# ccnor_stm32_v24-sync.net
KiCad netlist of a schematic drawn in EAGLE
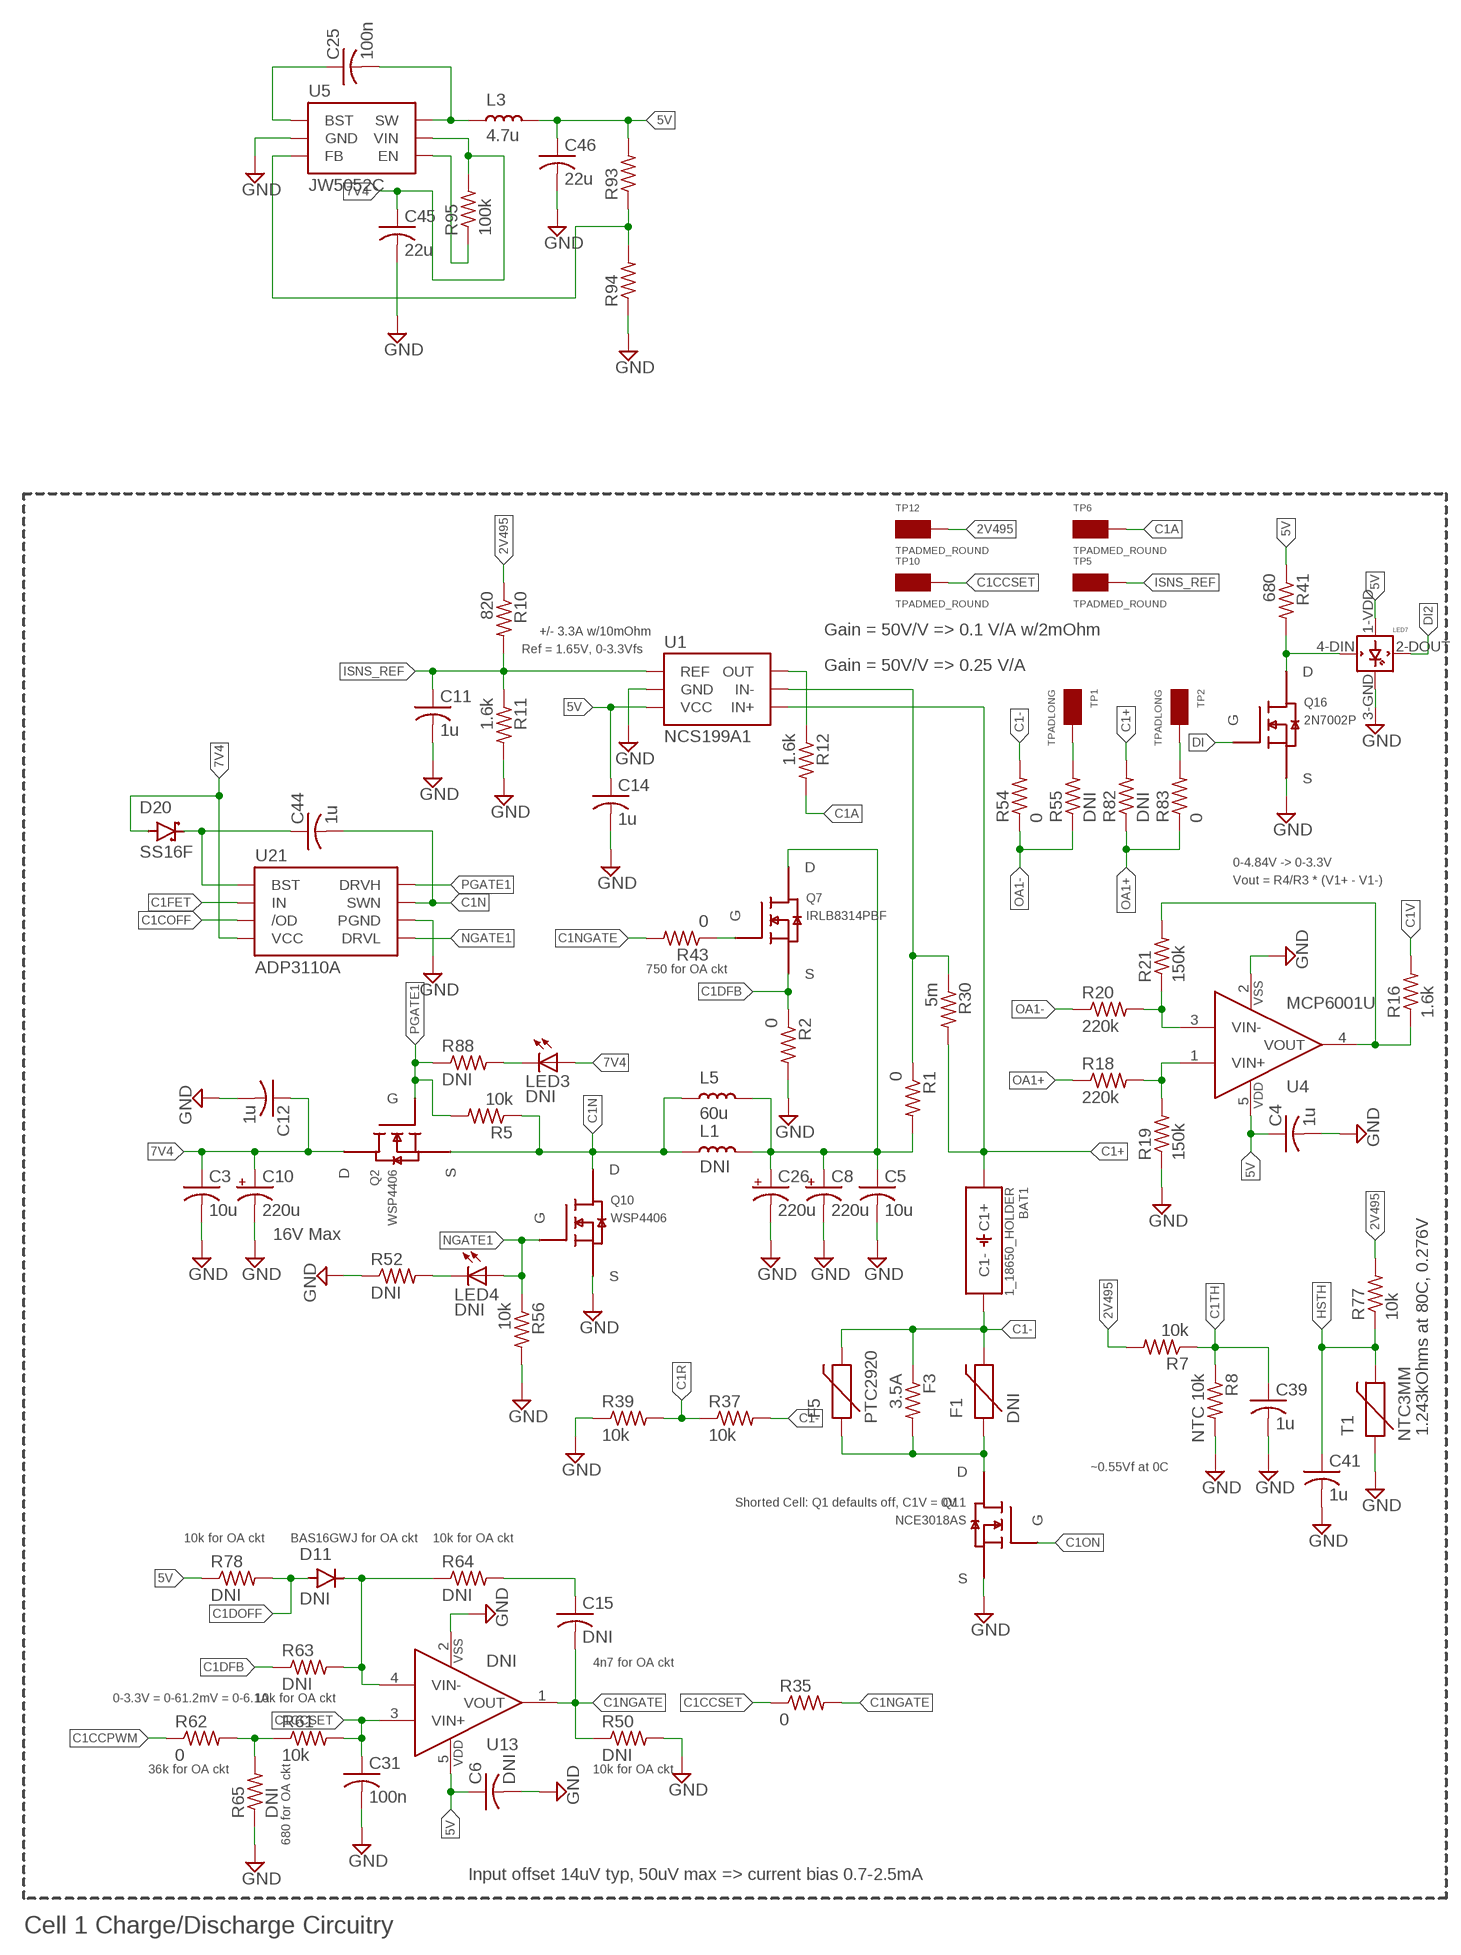
[diagram p0: schematic, sheet 1, part 1 of 2]
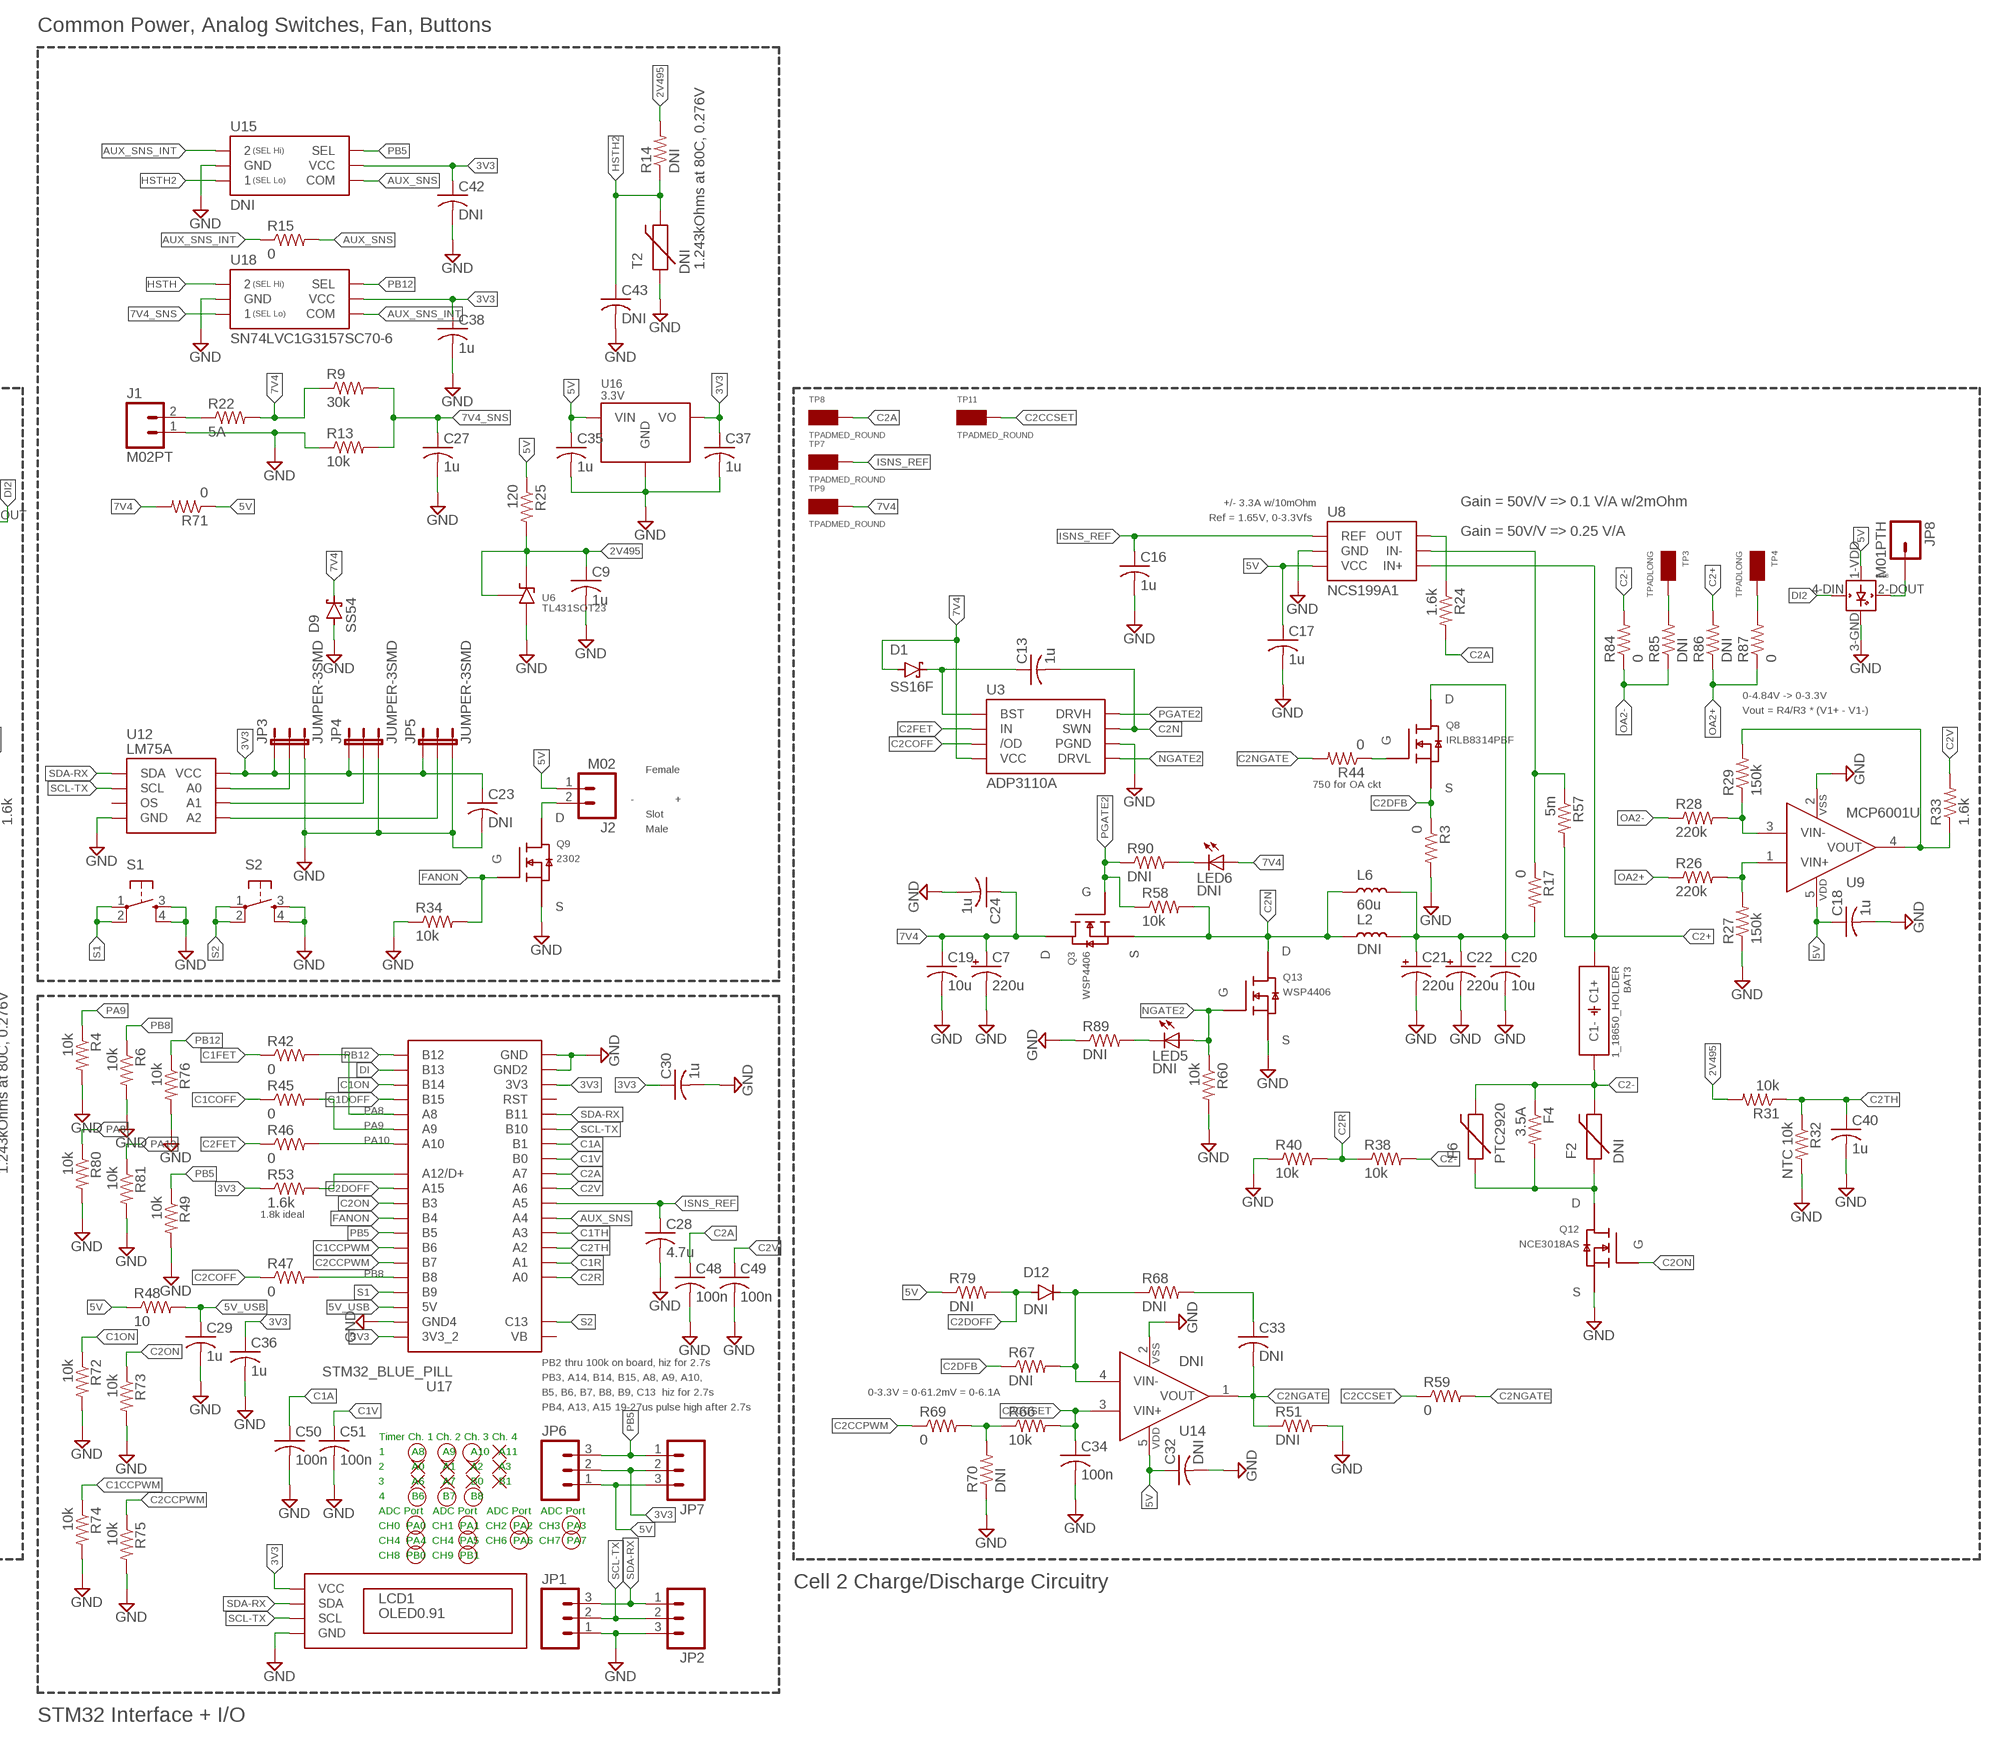
[diagram p1: schematic, sheet 1, part 2 of 2]

(export (version "E")
  (design (tool "Eeschema 10.0.6"))
  (components
    (comp (ref "BAT1")
      (value "1_18650_HOLDER")
      (footprint "eagle-import:1S_18650_SMD_NH")
      (libsource (lib "eagle-import") (part "1_18650_HOLDER"))
    )
    (comp (ref "BAT3")
      (value "1_18650_HOLDER")
      (footprint "eagle-import:1S_18650_SMD_NH")
      (libsource (lib "eagle-import") (part "1_18650_HOLDER"))
    )
    (comp (ref "C3")
      (value "10u")
      (footprint "eagle-import:C1206")
      (libsource (lib "eagle-import") (part "C-USC1206"))
    )
    (comp (ref "C4")
      (value "1u")
      (footprint "eagle-import:C0402")
      (libsource (lib "eagle-import") (part "C-USC0402"))
    )
    (comp (ref "C5")
      (value "10u")
      (footprint "eagle-import:C1206")
      (libsource (lib "eagle-import") (part "C-USC1206"))
    )
    (comp (ref "C6")
      (value "DNI")
      (footprint "eagle-import:C0402")
      (libsource (lib "eagle-import") (part "C-USC0402"))
    )
    (comp (ref "C7")
      (value "220u")
      (footprint "eagle-import:PANASONIC_D")
      (libsource (lib "eagle-import") (part "CPOL-USD"))
    )
    (comp (ref "C8")
      (value "220u")
      (footprint "eagle-import:PANASONIC_D")
      (libsource (lib "eagle-import") (part "CPOL-USD"))
    )
    (comp (ref "C9")
      (value "1u")
      (footprint "eagle-import:C0402")
      (libsource (lib "eagle-import") (part "C-USC0402"))
    )
    (comp (ref "C10")
      (value "220u")
      (footprint "eagle-import:PANASONIC_D")
      (libsource (lib "eagle-import") (part "CPOL-USD"))
    )
    (comp (ref "C11")
      (value "1u")
      (footprint "eagle-import:C0402")
      (libsource (lib "eagle-import") (part "C-USC0402"))
    )
    (comp (ref "C12")
      (value "1u")
      (footprint "eagle-import:C0402")
      (libsource (lib "eagle-import") (part "C-USC0402"))
    )
    (comp (ref "C13")
      (value "1u")
      (footprint "eagle-import:C0603")
      (libsource (lib "eagle-import") (part "C-USC0603"))
    )
    (comp (ref "C14")
      (value "1u")
      (footprint "eagle-import:C0402")
      (libsource (lib "eagle-import") (part "C-USC0402"))
    )
    (comp (ref "C15")
      (value "DNI")
      (footprint "eagle-import:C0402")
      (libsource (lib "eagle-import") (part "C-USC0402"))
    )
    (comp (ref "C16")
      (value "1u")
      (footprint "eagle-import:C0402")
      (libsource (lib "eagle-import") (part "C-USC0402"))
    )
    (comp (ref "C17")
      (value "1u")
      (footprint "eagle-import:C0402")
      (libsource (lib "eagle-import") (part "C-USC0402"))
    )
    (comp (ref "C18")
      (value "1u")
      (footprint "eagle-import:C0402")
      (libsource (lib "eagle-import") (part "C-USC0402"))
    )
    (comp (ref "C19")
      (value "10u")
      (footprint "eagle-import:C1206")
      (libsource (lib "eagle-import") (part "C-USC1206"))
    )
    (comp (ref "C20")
      (value "10u")
      (footprint "eagle-import:C1206")
      (libsource (lib "eagle-import") (part "C-USC1206"))
    )
    (comp (ref "C21")
      (value "220u")
      (footprint "eagle-import:PANASONIC_D")
      (libsource (lib "eagle-import") (part "CPOL-USD"))
    )
    (comp (ref "C22")
      (value "220u")
      (footprint "eagle-import:PANASONIC_D")
      (libsource (lib "eagle-import") (part "CPOL-USD"))
    )
    (comp (ref "C23")
      (value "DNI")
      (footprint "eagle-import:C0402")
      (libsource (lib "eagle-import") (part "C-USC0402"))
    )
    (comp (ref "C24")
      (value "1u")
      (footprint "eagle-import:C0402")
      (libsource (lib "eagle-import") (part "C-USC0402"))
    )
    (comp (ref "C25")
      (value "100n")
      (footprint "eagle-import:C0402")
      (libsource (lib "eagle-import") (part "C-USC0402"))
    )
    (comp (ref "C26")
      (value "220u")
      (footprint "eagle-import:PANASONIC_D")
      (libsource (lib "eagle-import") (part "CPOL-USD"))
    )
    (comp (ref "C27")
      (value "1u")
      (footprint "eagle-import:C0402")
      (libsource (lib "eagle-import") (part "C-USC0402"))
    )
    (comp (ref "C28")
      (value "4.7u")
      (footprint "eagle-import:C0402")
      (libsource (lib "eagle-import") (part "C-USC0402"))
    )
    (comp (ref "C29")
      (value "1u")
      (footprint "eagle-import:C0402")
      (libsource (lib "eagle-import") (part "C-USC0402"))
    )
    (comp (ref "C30")
      (value "1u")
      (footprint "eagle-import:C0402")
      (libsource (lib "eagle-import") (part "C-USC0402"))
    )
    (comp (ref "C31")
      (value "100n")
      (footprint "eagle-import:C0402")
      (libsource (lib "eagle-import") (part "C-USC0402"))
    )
    (comp (ref "C32")
      (value "DNI")
      (footprint "eagle-import:C0402")
      (libsource (lib "eagle-import") (part "C-USC0402"))
    )
    (comp (ref "C33")
      (value "DNI")
      (footprint "eagle-import:C0402")
      (libsource (lib "eagle-import") (part "C-USC0402"))
    )
    (comp (ref "C34")
      (value "100n")
      (footprint "eagle-import:C0402")
      (libsource (lib "eagle-import") (part "C-USC0402"))
    )
    (comp (ref "C35")
      (value "1u")
      (footprint "eagle-import:C0402")
      (libsource (lib "eagle-import") (part "C-USC0402"))
    )
    (comp (ref "C36")
      (value "1u")
      (footprint "eagle-import:C0402")
      (libsource (lib "eagle-import") (part "C-USC0402"))
    )
    (comp (ref "C37")
      (value "1u")
      (footprint "eagle-import:C0402")
      (libsource (lib "eagle-import") (part "C-USC0402"))
    )
    (comp (ref "C38")
      (value "1u")
      (footprint "eagle-import:C0402")
      (libsource (lib "eagle-import") (part "C-USC0402"))
    )
    (comp (ref "C39")
      (value "1u")
      (footprint "eagle-import:C0402")
      (libsource (lib "eagle-import") (part "C-USC0402"))
    )
    (comp (ref "C40")
      (value "1u")
      (footprint "eagle-import:C0402")
      (libsource (lib "eagle-import") (part "C-USC0402"))
    )
    (comp (ref "C41")
      (value "1u")
      (footprint "eagle-import:C0402")
      (libsource (lib "eagle-import") (part "C-USC0402"))
    )
    (comp (ref "C42")
      (value "DNI")
      (footprint "eagle-import:C0402")
      (libsource (lib "eagle-import") (part "C-USC0402"))
    )
    (comp (ref "C43")
      (value "DNI")
      (footprint "eagle-import:C0402")
      (libsource (lib "eagle-import") (part "C-USC0402"))
    )
    (comp (ref "C44")
      (value "1u")
      (footprint "eagle-import:C0603")
      (libsource (lib "eagle-import") (part "C-USC0603"))
    )
    (comp (ref "C45")
      (value "22u")
      (footprint "eagle-import:C0805")
      (libsource (lib "eagle-import") (part "C-USC0805"))
    )
    (comp (ref "C46")
      (value "22u")
      (footprint "eagle-import:C0603")
      (libsource (lib "eagle-import") (part "C-USC0603"))
    )
    (comp (ref "C48")
      (value "100n")
      (footprint "eagle-import:C0402")
      (libsource (lib "eagle-import") (part "C-USC0402"))
    )
    (comp (ref "C49")
      (value "100n")
      (footprint "eagle-import:C0402")
      (libsource (lib "eagle-import") (part "C-USC0402"))
    )
    (comp (ref "C50")
      (value "100n")
      (footprint "eagle-import:C0402")
      (libsource (lib "eagle-import") (part "C-USC0402"))
    )
    (comp (ref "C51")
      (value "100n")
      (footprint "eagle-import:C0402")
      (libsource (lib "eagle-import") (part "C-USC0402"))
    )
    (comp (ref "D1")
      (value "SS16F")
      (footprint "eagle-import:SOD123")
      (libsource (lib "eagle-import") (part "DIODE_SCHOTTKYCDBM140-G"))
    )
    (comp (ref "D9")
      (value "SS54")
      (footprint "eagle-import:SMA")
      (libsource (lib "eagle-import") (part "SS54"))
    )
    (comp (ref "D11")
      (value "DNI")
      (footprint "eagle-import:SOD323")
      (libsource (lib "eagle-import") (part "BAT60A"))
    )
    (comp (ref "D12")
      (value "DNI")
      (footprint "eagle-import:SOD323")
      (libsource (lib "eagle-import") (part "BAT60A"))
    )
    (comp (ref "D20")
      (value "SS16F")
      (footprint "eagle-import:SOD123")
      (libsource (lib "eagle-import") (part "DIODE_SCHOTTKYCDBM140-G"))
    )
    (comp (ref "F1")
      (value "DNI")
      (footprint "eagle-import:1812")
      (libsource (lib "eagle-import") (part "PTC1812"))
    )
    (comp (ref "F2")
      (value "DNI")
      (footprint "eagle-import:1812")
      (libsource (lib "eagle-import") (part "PTC1812"))
    )
    (comp (ref "F3")
      (value "3.5A")
      (footprint "eagle-import:R1206")
      (libsource (lib "eagle-import") (part "R-US_R1206"))
    )
    (comp (ref "F4")
      (value "3.5A")
      (footprint "eagle-import:R1206")
      (libsource (lib "eagle-import") (part "R-US_R1206"))
    )
    (comp (ref "F5")
      (value "PTC2920")
      (footprint "eagle-import:2920")
      (libsource (lib "eagle-import") (part "PTC2920"))
    )
    (comp (ref "F6")
      (value "PTC2920")
      (footprint "eagle-import:2920")
      (libsource (lib "eagle-import") (part "PTC2920"))
    )
    (comp (ref "J1")
      (value "M02PT")
      (footprint "eagle-import:PHOENIXCONTACT1935161")
      (libsource (lib "eagle-import") (part "M02PT"))
    )
    (comp (ref "J2")
      (value "M02")
      (footprint "eagle-import:B2B-XH-A")
      (libsource (lib "eagle-import") (part "M02"))
    )
    (comp (ref "JP1")
      (value "M03PTH")
      (footprint "eagle-import:1X03")
      (libsource (lib "eagle-import") (part "M03PTH"))
    )
    (comp (ref "JP2")
      (value "M03PTH")
      (footprint "eagle-import:1X03")
      (libsource (lib "eagle-import") (part "M03PTH"))
    )
    (comp (ref "JP3")
      (value "JUMPER-3SMD")
      (footprint "eagle-import:SJ_3")
      (libsource (lib "eagle-import") (part "JUMPER-3SMD"))
    )
    (comp (ref "JP4")
      (value "JUMPER-3SMD")
      (footprint "eagle-import:SJ_3")
      (libsource (lib "eagle-import") (part "JUMPER-3SMD"))
    )
    (comp (ref "JP5")
      (value "JUMPER-3SMD")
      (footprint "eagle-import:SJ_3")
      (libsource (lib "eagle-import") (part "JUMPER-3SMD"))
    )
    (comp (ref "JP6")
      (value "M03PTH")
      (footprint "eagle-import:1X03")
      (libsource (lib "eagle-import") (part "M03PTH"))
    )
    (comp (ref "JP7")
      (value "M03PTH")
      (footprint "eagle-import:1X03")
      (libsource (lib "eagle-import") (part "M03PTH"))
    )
    (comp (ref "JP8")
      (value "M01PTH")
      (footprint "eagle-import:1X01")
      (libsource (lib "eagle-import") (part "M01PTH"))
    )
    (comp (ref "L1")
      (value "DNI")
      (footprint "eagle-import:INDUCTOR_SMD_13MM")
      (libsource (lib "eagle-import") (part "SDR1307"))
    )
    (comp (ref "L2")
      (value "DNI")
      (footprint "eagle-import:INDUCTOR_SMD_13MM")
      (libsource (lib "eagle-import") (part "SDR1307"))
    )
    (comp (ref "L3")
      (value "4.7u")
      (footprint "eagle-import:0805")
      (libsource (lib "eagle-import") (part "INDUCTOR0805"))
    )
    (comp (ref "L5")
      (value "60u")
      (footprint "eagle-import:INDUCTOR_10A_8.2MMX21MM")
      (libsource (lib "eagle-import") (part "INDUCTOR10A"))
    )
    (comp (ref "L6")
      (value "60u")
      (footprint "eagle-import:INDUCTOR_10A_8.2MMX21MM")
      (libsource (lib "eagle-import") (part "INDUCTOR10A"))
    )
    (comp (ref "LCD1")
      (value "OLED0.91")
      (footprint "eagle-import:OLED0.91")
      (libsource (lib "eagle-import") (part "OLED0.91"))
    )
    (comp (ref "LED3")
      (value "DNI")
      (footprint "eagle-import:CHIPLED_0603")
      (libsource (lib "eagle-import") (part "LEDCHIPLED_0603"))
    )
    (comp (ref "LED4")
      (value "DNI")
      (footprint "eagle-import:CHIPLED_0603")
      (libsource (lib "eagle-import") (part "LEDCHIPLED_0603"))
    )
    (comp (ref "LED5")
      (value "DNI")
      (footprint "eagle-import:CHIPLED_0603")
      (libsource (lib "eagle-import") (part "LEDCHIPLED_0603"))
    )
    (comp (ref "LED6")
      (value "DNI")
      (footprint "eagle-import:CHIPLED_0603")
      (libsource (lib "eagle-import") (part "LEDCHIPLED_0603"))
    )
    (comp (ref "LED7")
      (value "WS2812B")
      (footprint "eagle-import:WS2812B")
      (libsource (lib "eagle-import") (part "WS2812B"))
    )
    (comp (ref "LED8")
      (value "WS2812B")
      (footprint "eagle-import:WS2812B")
      (libsource (lib "eagle-import") (part "WS2812B"))
    )
    (comp (ref "Q2")
      (value "WSP4406")
      (footprint "eagle-import:8-SOIC")
      (libsource (lib "eagle-import") (part "N-MOSFET-SOIC8"))
    )
    (comp (ref "Q3")
      (value "WSP4406")
      (footprint "eagle-import:8-SOIC")
      (libsource (lib "eagle-import") (part "N-MOSFET-SOIC8"))
    )
    (comp (ref "Q7")
      (value "IRLB8314PBF")
      (footprint "eagle-import:TO-220")
      (libsource (lib "eagle-import") (part "IRLB8314PBF"))
    )
    (comp (ref "Q8")
      (value "IRLB8314PBF")
      (footprint "eagle-import:TO-220")
      (libsource (lib "eagle-import") (part "IRLB8314PBF"))
    )
    (comp (ref "Q9")
      (value "2302")
      (footprint "eagle-import:SOT23")
      (libsource (lib "eagle-import") (part "2N7002P"))
    )
    (comp (ref "Q10")
      (value "WSP4406")
      (footprint "eagle-import:8-SOIC")
      (libsource (lib "eagle-import") (part "N-MOSFET-SOIC8"))
    )
    (comp (ref "Q11")
      (value "NCE3018AS")
      (footprint "eagle-import:8-SOIC")
      (libsource (lib "eagle-import") (part "N-MOSFET-SOIC8"))
    )
    (comp (ref "Q12")
      (value "NCE3018AS")
      (footprint "eagle-import:8-SOIC")
      (libsource (lib "eagle-import") (part "N-MOSFET-SOIC8"))
    )
    (comp (ref "Q13")
      (value "WSP4406")
      (footprint "eagle-import:8-SOIC")
      (libsource (lib "eagle-import") (part "N-MOSFET-SOIC8"))
    )
    (comp (ref "Q16")
      (value "2N7002P")
      (footprint "eagle-import:SOT23")
      (libsource (lib "eagle-import") (part "2N7002P"))
    )
    (comp (ref "R1")
      (value "0")
      (footprint "eagle-import:R1206")
      (libsource (lib "eagle-import") (part "R-US_R1206"))
    )
    (comp (ref "R2")
      (value "0")
      (footprint "eagle-import:R1206")
      (libsource (lib "eagle-import") (part "R-US_R1206"))
    )
    (comp (ref "R3")
      (value "0")
      (footprint "eagle-import:R1206")
      (libsource (lib "eagle-import") (part "R-US_R1206"))
    )
    (comp (ref "R4")
      (value "10k")
      (footprint "eagle-import:R0402")
      (libsource (lib "eagle-import") (part "R-US_R0402"))
    )
    (comp (ref "R5")
      (value "10k")
      (footprint "eagle-import:R0402")
      (libsource (lib "eagle-import") (part "R-US_R0402"))
    )
    (comp (ref "R6")
      (value "10k")
      (footprint "eagle-import:R0402")
      (libsource (lib "eagle-import") (part "R-US_R0402"))
    )
    (comp (ref "R7")
      (value "10k")
      (footprint "eagle-import:R0402")
      (libsource (lib "eagle-import") (part "R-US_R0402"))
    )
    (comp (ref "R8")
      (value "NTC 10k")
      (footprint "eagle-import:R0402")
      (libsource (lib "eagle-import") (part "R-US_R0402"))
    )
    (comp (ref "R9")
      (value "30k")
      (footprint "eagle-import:R0402")
      (libsource (lib "eagle-import") (part "R-US_R0402"))
    )
    (comp (ref "R10")
      (value "820")
      (footprint "eagle-import:R0402")
      (libsource (lib "eagle-import") (part "R-US_R0402"))
    )
    (comp (ref "R11")
      (value "1.6k")
      (footprint "eagle-import:R0402")
      (libsource (lib "eagle-import") (part "R-US_R0402"))
    )
    (comp (ref "R12")
      (value "1.6k")
      (footprint "eagle-import:R0402")
      (libsource (lib "eagle-import") (part "R-US_R0402"))
    )
    (comp (ref "R13")
      (value "10k")
      (footprint "eagle-import:R0402")
      (libsource (lib "eagle-import") (part "R-US_R0402"))
    )
    (comp (ref "R14")
      (value "DNI")
      (footprint "eagle-import:R0402")
      (libsource (lib "eagle-import") (part "R-US_R0402"))
    )
    (comp (ref "R15")
      (value "0")
      (footprint "eagle-import:R0402")
      (libsource (lib "eagle-import") (part "R-US_R0402"))
    )
    (comp (ref "R16")
      (value "1.6k")
      (footprint "eagle-import:R0402")
      (libsource (lib "eagle-import") (part "R-US_R0402"))
    )
    (comp (ref "R17")
      (value "0")
      (footprint "eagle-import:R1206")
      (libsource (lib "eagle-import") (part "R-US_R1206"))
    )
    (comp (ref "R18")
      (value "220k")
      (footprint "eagle-import:R0402")
      (libsource (lib "eagle-import") (part "R-US_R0402"))
    )
    (comp (ref "R19")
      (value "150k")
      (footprint "eagle-import:R0402")
      (libsource (lib "eagle-import") (part "R-US_R0402"))
    )
    (comp (ref "R20")
      (value "220k")
      (footprint "eagle-import:R0402")
      (libsource (lib "eagle-import") (part "R-US_R0402"))
    )
    (comp (ref "R21")
      (value "150k")
      (footprint "eagle-import:R0402")
      (libsource (lib "eagle-import") (part "R-US_R0402"))
    )
    (comp (ref "R22")
      (value "5A")
      (footprint "eagle-import:R1206")
      (libsource (lib "eagle-import") (part "R-US_R1206"))
    )
    (comp (ref "R24")
      (value "1.6k")
      (footprint "eagle-import:R0402")
      (libsource (lib "eagle-import") (part "R-US_R0402"))
    )
    (comp (ref "R25")
      (value "120")
      (footprint "eagle-import:R0402")
      (libsource (lib "eagle-import") (part "R-US_R0402"))
    )
    (comp (ref "R26")
      (value "220k")
      (footprint "eagle-import:R0402")
      (libsource (lib "eagle-import") (part "R-US_R0402"))
    )
    (comp (ref "R27")
      (value "150k")
      (footprint "eagle-import:R0402")
      (libsource (lib "eagle-import") (part "R-US_R0402"))
    )
    (comp (ref "R28")
      (value "220k")
      (footprint "eagle-import:R0402")
      (libsource (lib "eagle-import") (part "R-US_R0402"))
    )
    (comp (ref "R29")
      (value "150k")
      (footprint "eagle-import:R0402")
      (libsource (lib "eagle-import") (part "R-US_R0402"))
    )
    (comp (ref "R30")
      (value "5m")
      (footprint "eagle-import:R1206")
      (libsource (lib "eagle-import") (part "R-US_R1206"))
    )
    (comp (ref "R31")
      (value "10k")
      (footprint "eagle-import:R0402")
      (libsource (lib "eagle-import") (part "R-US_R0402"))
    )
    (comp (ref "R32")
      (value "NTC 10k")
      (footprint "eagle-import:R0402")
      (libsource (lib "eagle-import") (part "R-US_R0402"))
    )
    (comp (ref "R33")
      (value "1.6k")
      (footprint "eagle-import:R0402")
      (libsource (lib "eagle-import") (part "R-US_R0402"))
    )
    (comp (ref "R34")
      (value "10k")
      (footprint "eagle-import:R0402")
      (libsource (lib "eagle-import") (part "R-US_R0402"))
    )
    (comp (ref "R35")
      (value "0")
      (footprint "eagle-import:R0402")
      (libsource (lib "eagle-import") (part "R-US_R0402"))
    )
    (comp (ref "R37")
      (value "10k")
      (footprint "eagle-import:R0402")
      (libsource (lib "eagle-import") (part "R-US_R0402"))
    )
    (comp (ref "R38")
      (value "10k")
      (footprint "eagle-import:R0402")
      (libsource (lib "eagle-import") (part "R-US_R0402"))
    )
    (comp (ref "R39")
      (value "10k")
      (footprint "eagle-import:R0402")
      (libsource (lib "eagle-import") (part "R-US_R0402"))
    )
    (comp (ref "R40")
      (value "10k")
      (footprint "eagle-import:R0402")
      (libsource (lib "eagle-import") (part "R-US_R0402"))
    )
    (comp (ref "R41")
      (value "680")
      (footprint "eagle-import:R0402")
      (libsource (lib "eagle-import") (part "R-US_R0402"))
    )
    (comp (ref "R42")
      (value "0")
      (footprint "eagle-import:R0402")
      (libsource (lib "eagle-import") (part "R-US_R0402"))
    )
    (comp (ref "R43")
      (value "0")
      (footprint "eagle-import:R0402")
      (libsource (lib "eagle-import") (part "R-US_R0402"))
    )
    (comp (ref "R44")
      (value "0")
      (footprint "eagle-import:R0402")
      (libsource (lib "eagle-import") (part "R-US_R0402"))
    )
    (comp (ref "R45")
      (value "0")
      (footprint "eagle-import:R0402")
      (libsource (lib "eagle-import") (part "R-US_R0402"))
    )
    (comp (ref "R46")
      (value "0")
      (footprint "eagle-import:R0402")
      (libsource (lib "eagle-import") (part "R-US_R0402"))
    )
    (comp (ref "R47")
      (value "0")
      (footprint "eagle-import:R0402")
      (libsource (lib "eagle-import") (part "R-US_R0402"))
    )
    (comp (ref "R48")
      (value "10")
      (footprint "eagle-import:R0402")
      (libsource (lib "eagle-import") (part "R-US_R0402"))
    )
    (comp (ref "R49")
      (value "10k")
      (footprint "eagle-import:R0402")
      (libsource (lib "eagle-import") (part "R-US_R0402"))
    )
    (comp (ref "R50")
      (value "DNI")
      (footprint "eagle-import:R0402")
      (libsource (lib "eagle-import") (part "R-US_R0402"))
    )
    (comp (ref "R51")
      (value "DNI")
      (footprint "eagle-import:R0402")
      (libsource (lib "eagle-import") (part "R-US_R0402"))
    )
    (comp (ref "R52")
      (value "DNI")
      (footprint "eagle-import:R0402")
      (libsource (lib "eagle-import") (part "R-US_R0402"))
    )
    (comp (ref "R53")
      (value "1.6k")
      (footprint "eagle-import:R0402")
      (libsource (lib "eagle-import") (part "R-US_R0402"))
    )
    (comp (ref "R54")
      (value "0")
      (footprint "eagle-import:R0402")
      (libsource (lib "eagle-import") (part "R-US_R0402"))
    )
    (comp (ref "R55")
      (value "DNI")
      (footprint "eagle-import:R0402")
      (libsource (lib "eagle-import") (part "R-US_R0402"))
    )
    (comp (ref "R56")
      (value "10k")
      (footprint "eagle-import:R0402")
      (libsource (lib "eagle-import") (part "R-US_R0402"))
    )
    (comp (ref "R57")
      (value "5m")
      (footprint "eagle-import:R1206")
      (libsource (lib "eagle-import") (part "R-US_R1206"))
    )
    (comp (ref "R58")
      (value "10k")
      (footprint "eagle-import:R0402")
      (libsource (lib "eagle-import") (part "R-US_R0402"))
    )
    (comp (ref "R59")
      (value "0")
      (footprint "eagle-import:R0402")
      (libsource (lib "eagle-import") (part "R-US_R0402"))
    )
    (comp (ref "R60")
      (value "10k")
      (footprint "eagle-import:R0402")
      (libsource (lib "eagle-import") (part "R-US_R0402"))
    )
    (comp (ref "R61")
      (value "10k")
      (footprint "eagle-import:R0402")
      (libsource (lib "eagle-import") (part "R-US_R0402"))
    )
    (comp (ref "R62")
      (value "0")
      (footprint "eagle-import:R0402")
      (libsource (lib "eagle-import") (part "R-US_R0402"))
    )
    (comp (ref "R63")
      (value "DNI")
      (footprint "eagle-import:R0402")
      (libsource (lib "eagle-import") (part "R-US_R0402"))
    )
    (comp (ref "R64")
      (value "DNI")
      (footprint "eagle-import:R0402")
      (libsource (lib "eagle-import") (part "R-US_R0402"))
    )
    (comp (ref "R65")
      (value "DNI")
      (footprint "eagle-import:R0402")
      (libsource (lib "eagle-import") (part "R-US_R0402"))
    )
    (comp (ref "R66")
      (value "10k")
      (footprint "eagle-import:R0402")
      (libsource (lib "eagle-import") (part "R-US_R0402"))
    )
    (comp (ref "R67")
      (value "DNI")
      (footprint "eagle-import:R0402")
      (libsource (lib "eagle-import") (part "R-US_R0402"))
    )
    (comp (ref "R68")
      (value "DNI")
      (footprint "eagle-import:R0402")
      (libsource (lib "eagle-import") (part "R-US_R0402"))
    )
    (comp (ref "R69")
      (value "0")
      (footprint "eagle-import:R0402")
      (libsource (lib "eagle-import") (part "R-US_R0402"))
    )
    (comp (ref "R70")
      (value "DNI")
      (footprint "eagle-import:R0402")
      (libsource (lib "eagle-import") (part "R-US_R0402"))
    )
    (comp (ref "R71")
      (value "0")
      (footprint "eagle-import:R0603")
      (libsource (lib "eagle-import") (part "R-US_R0603"))
    )
    (comp (ref "R72")
      (value "10k")
      (footprint "eagle-import:R0402")
      (libsource (lib "eagle-import") (part "R-US_R0402"))
    )
    (comp (ref "R73")
      (value "10k")
      (footprint "eagle-import:R0402")
      (libsource (lib "eagle-import") (part "R-US_R0402"))
    )
    (comp (ref "R74")
      (value "10k")
      (footprint "eagle-import:R0402")
      (libsource (lib "eagle-import") (part "R-US_R0402"))
    )
    (comp (ref "R75")
      (value "10k")
      (footprint "eagle-import:R0402")
      (libsource (lib "eagle-import") (part "R-US_R0402"))
    )
    (comp (ref "R76")
      (value "10k")
      (footprint "eagle-import:R0402")
      (libsource (lib "eagle-import") (part "R-US_R0402"))
    )
    (comp (ref "R77")
      (value "10k")
      (footprint "eagle-import:R0402")
      (libsource (lib "eagle-import") (part "R-US_R0402"))
    )
    (comp (ref "R78")
      (value "DNI")
      (footprint "eagle-import:R0402")
      (libsource (lib "eagle-import") (part "R-US_R0402"))
    )
    (comp (ref "R79")
      (value "DNI")
      (footprint "eagle-import:R0402")
      (libsource (lib "eagle-import") (part "R-US_R0402"))
    )
    (comp (ref "R80")
      (value "10k")
      (footprint "eagle-import:R0402")
      (libsource (lib "eagle-import") (part "R-US_R0402"))
    )
    (comp (ref "R81")
      (value "10k")
      (footprint "eagle-import:R0402")
      (libsource (lib "eagle-import") (part "R-US_R0402"))
    )
    (comp (ref "R82")
      (value "DNI")
      (footprint "eagle-import:R0402")
      (libsource (lib "eagle-import") (part "R-US_R0402"))
    )
    (comp (ref "R83")
      (value "0")
      (footprint "eagle-import:R0402")
      (libsource (lib "eagle-import") (part "R-US_R0402"))
    )
    (comp (ref "R84")
      (value "0")
      (footprint "eagle-import:R0402")
      (libsource (lib "eagle-import") (part "R-US_R0402"))
    )
    (comp (ref "R85")
      (value "DNI")
      (footprint "eagle-import:R0402")
      (libsource (lib "eagle-import") (part "R-US_R0402"))
    )
    (comp (ref "R86")
      (value "DNI")
      (footprint "eagle-import:R0402")
      (libsource (lib "eagle-import") (part "R-US_R0402"))
    )
    (comp (ref "R87")
      (value "0")
      (footprint "eagle-import:R0402")
      (libsource (lib "eagle-import") (part "R-US_R0402"))
    )
    (comp (ref "R88")
      (value "DNI")
      (footprint "eagle-import:R0402")
      (libsource (lib "eagle-import") (part "R-US_R0402"))
    )
    (comp (ref "R89")
      (value "DNI")
      (footprint "eagle-import:R0402")
      (libsource (lib "eagle-import") (part "R-US_R0402"))
    )
    (comp (ref "R90")
      (value "DNI")
      (footprint "eagle-import:R0402")
      (libsource (lib "eagle-import") (part "R-US_R0402"))
    )
    (comp (ref "R93")
      (value "R-US_R0402")
      (footprint "eagle-import:R0402")
      (libsource (lib "eagle-import") (part "R-US_R0402"))
    )
    (comp (ref "R94")
      (value "R-US_R0402")
      (footprint "eagle-import:R0402")
      (libsource (lib "eagle-import") (part "R-US_R0402"))
    )
    (comp (ref "R95")
      (value "100k")
      (footprint "eagle-import:R0402")
      (libsource (lib "eagle-import") (part "R-US_R0402"))
    )
    (comp (ref "S1")
      (value "TAC_SWITCHSMD")
      (footprint "eagle-import:TACTILE_SWITCH_SMD")
      (libsource (lib "eagle-import") (part "TAC_SWITCHSMD"))
    )
    (comp (ref "S2")
      (value "TAC_SWITCHSMD")
      (footprint "eagle-import:TACTILE_SWITCH_SMD")
      (libsource (lib "eagle-import") (part "TAC_SWITCHSMD"))
    )
    (comp (ref "T1")
      (value "NTC3MM")
      (footprint "eagle-import:THERMISTOR_3MMX3MM")
      (libsource (lib "eagle-import") (part "PTCNTC3MM"))
    )
    (comp (ref "T2")
      (value "DNI")
      (footprint "eagle-import:THERMISTOR_3MMX3MM")
      (libsource (lib "eagle-import") (part "PTCNTC3MM"))
    )
    (comp (ref "TP1")
      (value "TPADLONG")
      (footprint "eagle-import:TPAD_LONG")
      (libsource (lib "eagle-import") (part "TPADLONG"))
    )
    (comp (ref "TP2")
      (value "TPADLONG")
      (footprint "eagle-import:TPAD_LONG")
      (libsource (lib "eagle-import") (part "TPADLONG"))
    )
    (comp (ref "TP3")
      (value "TPADLONG")
      (footprint "eagle-import:TPAD_LONG")
      (libsource (lib "eagle-import") (part "TPADLONG"))
    )
    (comp (ref "TP4")
      (value "TPADLONG")
      (footprint "eagle-import:TPAD_LONG")
      (libsource (lib "eagle-import") (part "TPADLONG"))
    )
    (comp (ref "TP5")
      (value "TPADMED_ROUND")
      (footprint "eagle-import:TPAD_MED_ROUND")
      (libsource (lib "eagle-import") (part "TPADMED_ROUND"))
    )
    (comp (ref "TP6")
      (value "TPADMED_ROUND")
      (footprint "eagle-import:TPAD_MED_ROUND")
      (libsource (lib "eagle-import") (part "TPADMED_ROUND"))
    )
    (comp (ref "TP7")
      (value "TPADMED_ROUND")
      (footprint "eagle-import:TPAD_MED_ROUND")
      (libsource (lib "eagle-import") (part "TPADMED_ROUND"))
    )
    (comp (ref "TP8")
      (value "TPADMED_ROUND")
      (footprint "eagle-import:TPAD_MED_ROUND")
      (libsource (lib "eagle-import") (part "TPADMED_ROUND"))
    )
    (comp (ref "TP9")
      (value "TPADMED_ROUND")
      (footprint "eagle-import:TPAD_MED_ROUND")
      (libsource (lib "eagle-import") (part "TPADMED_ROUND"))
    )
    (comp (ref "TP10")
      (value "TPADMED_ROUND")
      (footprint "eagle-import:TPAD_MED_ROUND")
      (libsource (lib "eagle-import") (part "TPADMED_ROUND"))
    )
    (comp (ref "TP11")
      (value "TPADMED_ROUND")
      (footprint "eagle-import:TPAD_MED_ROUND")
      (libsource (lib "eagle-import") (part "TPADMED_ROUND"))
    )
    (comp (ref "TP12")
      (value "TPADMED_ROUND")
      (footprint "eagle-import:TPAD_MED_ROUND")
      (libsource (lib "eagle-import") (part "TPADMED_ROUND"))
    )
    (comp (ref "U1")
      (value "NCS199A1")
      (footprint "eagle-import:SOT-363")
      (libsource (lib "eagle-import") (part "INA214"))
    )
    (comp (ref "U3")
      (value "ADP3110A")
      (footprint "eagle-import:8-SOIC")
      (libsource (lib "eagle-import") (part "ADP3110A"))
    )
    (comp (ref "U4")
      (value "MCP6001U")
      (footprint "eagle-import:SOT23-5")
      (libsource (lib "eagle-import") (part "MCP6001U"))
    )
    (comp (ref "U5")
      (value "JW5052C")
      (footprint "eagle-import:SOT23-6")
      (libsource (lib "eagle-import") (part "JW5052C"))
    )
    (comp (ref "U6")
      (value "TL431SOT23")
      (footprint "eagle-import:SOT23")
      (libsource (lib "eagle-import") (part "TL431SOT23"))
    )
    (comp (ref "U8")
      (value "NCS199A1")
      (footprint "eagle-import:SOT-363")
      (libsource (lib "eagle-import") (part "INA214"))
    )
    (comp (ref "U9")
      (value "MCP6001U")
      (footprint "eagle-import:SOT23-5")
      (libsource (lib "eagle-import") (part "MCP6001U"))
    )
    (comp (ref "U12")
      (value "LM75A")
      (footprint "eagle-import:8-SOIC")
      (libsource (lib "eagle-import") (part "LM75A"))
    )
    (comp (ref "U13")
      (value "DNI")
      (footprint "eagle-import:SOT23-5")
      (libsource (lib "eagle-import") (part "NCS325"))
    )
    (comp (ref "U14")
      (value "DNI")
      (footprint "eagle-import:SOT23-5")
      (libsource (lib "eagle-import") (part "NCS325"))
    )
    (comp (ref "U15")
      (value "DNI")
      (footprint "eagle-import:SC70-6")
      (libsource (lib "eagle-import") (part "SN74LVC1G3157SC70-6"))
    )
    (comp (ref "U16")
      (value "3.3V")
      (footprint "eagle-import:SOT-89")
      (libsource (lib "eagle-import") (part "AP1117UR133-B"))
    )
    (comp (ref "U17")
      (value "STM32_BLUE_PILL")
      (footprint "eagle-import:STM32_BLUE_PILL_USABLE")
      (libsource (lib "eagle-import") (part "STM32_BLUE_PILL"))
    )
    (comp (ref "U18")
      (value "SN74LVC1G3157SC70-6")
      (footprint "eagle-import:SC70-6")
      (libsource (lib "eagle-import") (part "SN74LVC1G3157SC70-6"))
    )
    (comp (ref "U21")
      (value "ADP3110A")
      (footprint "eagle-import:8-SOIC")
      (libsource (lib "eagle-import") (part "ADP3110A"))
    )
  )
  (nets
    (net (code "1") (name "2V495") (class "Default")
      (node (ref "C9") (pin "1") (pinfunction "1_1") (pintype "passive"))
      (node (ref "R10") (pin "1") (pinfunction "1_1") (pintype "passive"))
      (node (ref "R14") (pin "2") (pinfunction "2_2") (pintype "passive"))
      (node (ref "R25") (pin "2") (pinfunction "2_2") (pintype "passive"))
      (node (ref "R31") (pin "2") (pinfunction "2_2") (pintype "passive"))
      (node (ref "R7") (pin "2") (pinfunction "2_2") (pintype "passive"))
      (node (ref "R77") (pin "2") (pinfunction "2_2") (pintype "passive"))
      (node (ref "TP12") (pin "1") (pinfunction "1_1") (pintype "bidirectional"))
      (node (ref "U6") (pin "1") (pinfunction "K_1") (pintype "passive"))
      (node (ref "U6") (pin "2") (pinfunction "REF_2") (pintype "passive"))
    )
    (net (code "2") (name "3V3") (class "Default")
      (node (ref "C23") (pin "1") (pinfunction "1_1") (pintype "passive"))
      (node (ref "C30") (pin "1") (pinfunction "1_1") (pintype "passive"))
      (node (ref "C36") (pin "1") (pinfunction "1_1") (pintype "passive"))
      (node (ref "C37") (pin "1") (pinfunction "1_1") (pintype "passive"))
      (node (ref "C38") (pin "1") (pinfunction "1_1") (pintype "passive"))
      (node (ref "C42") (pin "1") (pinfunction "1_1") (pintype "passive"))
      (node (ref "JP3") (pin "1") (pinfunction "1_1") (pintype "passive"))
      (node (ref "JP4") (pin "1") (pinfunction "1_1") (pintype "passive"))
      (node (ref "JP5") (pin "1") (pinfunction "1_1") (pintype "passive"))
      (node (ref "JP6") (pin "2") (pinfunction "2_2") (pintype "passive"))
      (node (ref "JP7") (pin "2") (pinfunction "2_2") (pintype "passive"))
      (node (ref "LCD1") (pin "2-VCC") (pinfunction "VCC_2-VCC") (pintype "bidirectional"))
      (node (ref "R53") (pin "1") (pinfunction "1_1") (pintype "passive"))
      (node (ref "U12") (pin "8") (pinfunction "VCC_8") (pintype "bidirectional"))
      (node (ref "U15") (pin "5") (pinfunction "VCC_5") (pintype "bidirectional"))
      (node (ref "U16") (pin "1") (pinfunction "VO_1") (pintype "bidirectional"))
      (node (ref "U17") (pin "3V3") (pinfunction "3V3_3V3") (pintype "bidirectional"))
      (node (ref "U17") (pin "3V3_2") (pinfunction "3V3_2_3V3_2") (pintype "bidirectional"))
      (node (ref "U18") (pin "5") (pinfunction "VCC_5") (pintype "bidirectional"))
    )
    (net (code "3") (name "5V") (class "Default")
      (node (ref "C14") (pin "1") (pinfunction "1_1") (pintype "passive"))
      (node (ref "C17") (pin "1") (pinfunction "1_1") (pintype "passive"))
      (node (ref "C18") (pin "1") (pinfunction "1_1") (pintype "passive"))
      (node (ref "C32") (pin "1") (pinfunction "1_1") (pintype "passive"))
      (node (ref "C35") (pin "1") (pinfunction "1_1") (pintype "passive"))
      (node (ref "C4") (pin "1") (pinfunction "1_1") (pintype "passive"))
      (node (ref "C46") (pin "1") (pinfunction "1_1") (pintype "passive"))
      (node (ref "C6") (pin "1") (pinfunction "1_1") (pintype "passive"))
      (node (ref "J2") (pin "1") (pinfunction "1_1") (pintype "passive"))
      (node (ref "JP6") (pin "1") (pinfunction "1_1") (pintype "passive"))
      (node (ref "JP7") (pin "3") (pinfunction "3_3") (pintype "passive"))
      (node (ref "L3") (pin "2") (pinfunction "P$2_2") (pintype "passive"))
      (node (ref "LED7") (pin "1-VDD") (pinfunction "VDD_1-VDD") (pintype "bidirectional"))
      (node (ref "LED8") (pin "1-VDD") (pinfunction "VDD_1-VDD") (pintype "bidirectional"))
      (node (ref "R25") (pin "1") (pinfunction "1_1") (pintype "passive"))
      (node (ref "R41") (pin "1") (pinfunction "1_1") (pintype "passive"))
      (node (ref "R48") (pin "1") (pinfunction "1_1") (pintype "passive"))
      (node (ref "R71") (pin "1") (pinfunction "1_1") (pintype "passive"))
      (node (ref "R78") (pin "1") (pinfunction "1_1") (pintype "passive"))
      (node (ref "R79") (pin "1") (pinfunction "1_1") (pintype "passive"))
      (node (ref "R93") (pin "2") (pinfunction "2_2") (pintype "passive"))
      (node (ref "U1") (pin "3") (pinfunction "VCC_3") (pintype "bidirectional"))
      (node (ref "U13") (pin "5") (pinfunction "VDD_5") (pintype "bidirectional"))
      (node (ref "U14") (pin "5") (pinfunction "VDD_5") (pintype "bidirectional"))
      (node (ref "U16") (pin "3") (pinfunction "VIN_3") (pintype "bidirectional"))
      (node (ref "U4") (pin "5") (pinfunction "VDD_5") (pintype "bidirectional"))
      (node (ref "U8") (pin "3") (pinfunction "VCC_3") (pintype "bidirectional"))
      (node (ref "U9") (pin "5") (pinfunction "VDD_5") (pintype "bidirectional"))
    )
    (net (code "4") (name "5V_USB") (class "Default")
      (node (ref "C29") (pin "1") (pinfunction "1_1") (pintype "passive"))
      (node (ref "R48") (pin "2") (pinfunction "2_2") (pintype "passive"))
      (node (ref "U17") (pin "5V") (pinfunction "5V_5V") (pintype "bidirectional"))
    )
    (net (code "5") (name "7V4") (class "Default")
      (node (ref "C10") (pin "+") (pinfunction "+_+") (pintype "passive"))
      (node (ref "C12") (pin "1") (pinfunction "1_1") (pintype "passive"))
      (node (ref "C19") (pin "1") (pinfunction "1_1") (pintype "passive"))
      (node (ref "C24") (pin "1") (pinfunction "1_1") (pintype "passive"))
      (node (ref "C3") (pin "1") (pinfunction "1_1") (pintype "passive"))
      (node (ref "C45") (pin "1") (pinfunction "1_1") (pintype "passive"))
      (node (ref "C7") (pin "+") (pinfunction "+_+") (pintype "passive"))
      (node (ref "D1") (pin "A") (pinfunction "ANODE_A") (pintype "passive"))
      (node (ref "D20") (pin "A") (pinfunction "ANODE_A") (pintype "passive"))
      (node (ref "D9") (pin "K") (pinfunction "CATHODE_K") (pintype "passive"))
      (node (ref "LED3") (pin "A") (pinfunction "A_A") (pintype "passive"))
      (node (ref "LED6") (pin "A") (pinfunction "A_A") (pintype "passive"))
      (node (ref "Q2") (pin "5") (pinfunction "D_5") (pintype "bidirectional"))
      (node (ref "Q2") (pin "6") (pinfunction "D_6") (pintype "bidirectional"))
      (node (ref "Q2") (pin "7") (pinfunction "D_7") (pintype "bidirectional"))
      (node (ref "Q2") (pin "8") (pinfunction "D_8") (pintype "bidirectional"))
      (node (ref "Q3") (pin "5") (pinfunction "D_5") (pintype "bidirectional"))
      (node (ref "Q3") (pin "6") (pinfunction "D_6") (pintype "bidirectional"))
      (node (ref "Q3") (pin "7") (pinfunction "D_7") (pintype "bidirectional"))
      (node (ref "Q3") (pin "8") (pinfunction "D_8") (pintype "bidirectional"))
      (node (ref "R22") (pin "2") (pinfunction "2_2") (pintype "passive"))
      (node (ref "R71") (pin "2") (pinfunction "2_2") (pintype "passive"))
      (node (ref "R9") (pin "1") (pinfunction "1_1") (pintype "passive"))
      (node (ref "R95") (pin "2") (pinfunction "2_2") (pintype "passive"))
      (node (ref "TP9") (pin "1") (pinfunction "1_1") (pintype "bidirectional"))
      (node (ref "U21") (pin "4") (pinfunction "VCC_4") (pintype "bidirectional"))
      (node (ref "U3") (pin "4") (pinfunction "VCC_4") (pintype "bidirectional"))
      (node (ref "U5") (pin "5") (pinfunction "VIN_5") (pintype "bidirectional"))
    )
    (net (code "6") (name "7V4_SNS") (class "Default")
      (node (ref "C27") (pin "1") (pinfunction "1_1") (pintype "passive"))
      (node (ref "R13") (pin "2") (pinfunction "2_2") (pintype "passive"))
      (node (ref "R9") (pin "2") (pinfunction "2_2") (pintype "passive"))
      (node (ref "U18") (pin "3") (pinfunction "1_3") (pintype "bidirectional"))
    )
    (net (code "7") (name "AUX_SNS") (class "Default")
      (node (ref "R15") (pin "2") (pinfunction "2_2") (pintype "passive"))
      (node (ref "U15") (pin "4") (pinfunction "COM_4") (pintype "bidirectional"))
      (node (ref "U17") (pin "A4") (pinfunction "A4_A4") (pintype "bidirectional"))
    )
    (net (code "8") (name "AUX_SNS_INT") (class "Default")
      (node (ref "R15") (pin "1") (pinfunction "1_1") (pintype "passive"))
      (node (ref "U15") (pin "1") (pinfunction "2_1") (pintype "bidirectional"))
      (node (ref "U18") (pin "4") (pinfunction "COM_4") (pintype "bidirectional"))
    )
    (net (code "9") (name "C1+") (class "Default")
      (node (ref "BAT1") (pin "1+") (pinfunction "C1+_1+") (pintype "bidirectional"))
      (node (ref "R30") (pin "2") (pinfunction "2_2") (pintype "passive"))
      (node (ref "R82") (pin "2") (pinfunction "2_2") (pintype "passive"))
      (node (ref "U1") (pin "4") (pinfunction "IN+_4") (pintype "bidirectional"))
    )
    (net (code "10") (name "C1-") (class "Default")
      (node (ref "BAT1") (pin "1-") (pinfunction "C1-_1-") (pintype "bidirectional"))
      (node (ref "F1") (pin "2") (pinfunction "2_2") (pintype "bidirectional"))
      (node (ref "F3") (pin "1") (pinfunction "1_1") (pintype "passive"))
      (node (ref "F5") (pin "K") (pinfunction "2_K") (pintype "bidirectional"))
      (node (ref "R37") (pin "2") (pinfunction "2_2") (pintype "passive"))
      (node (ref "R54") (pin "2") (pinfunction "2_2") (pintype "passive"))
    )
    (net (code "11") (name "C1A") (class "Default")
      (node (ref "C50") (pin "1") (pinfunction "1_1") (pintype "passive"))
      (node (ref "R12") (pin "2") (pinfunction "2_2") (pintype "passive"))
      (node (ref "TP6") (pin "1") (pinfunction "1_1") (pintype "bidirectional"))
      (node (ref "U17") (pin "B1") (pinfunction "B1_B1") (pintype "bidirectional"))
    )
    (net (code "12") (name "C1CCPWM") (class "Default")
      (node (ref "R62") (pin "1") (pinfunction "1_1") (pintype "passive"))
      (node (ref "R74") (pin "1") (pinfunction "1_1") (pintype "passive"))
      (node (ref "U17") (pin "B6") (pinfunction "B6_B6") (pintype "bidirectional"))
    )
    (net (code "13") (name "C1CCSET") (class "Default")
      (node (ref "C31") (pin "1") (pinfunction "1_1") (pintype "passive"))
      (node (ref "R35") (pin "1") (pinfunction "1_1") (pintype "passive"))
      (node (ref "R61") (pin "2") (pinfunction "2_2") (pintype "passive"))
      (node (ref "TP10") (pin "1") (pinfunction "1_1") (pintype "bidirectional"))
      (node (ref "U13") (pin "3") (pinfunction "VIN+_3") (pintype "bidirectional"))
    )
    (net (code "14") (name "C1COFF") (class "Default")
      (node (ref "R45") (pin "1") (pinfunction "1_1") (pintype "passive"))
      (node (ref "U21") (pin "3") (pinfunction "/OD_3") (pintype "bidirectional"))
    )
    (net (code "15") (name "C1DFB") (class "Default")
      (node (ref "Q7") (pin "3") (pinfunction "S_3") (pintype "bidirectional"))
      (node (ref "R2") (pin "1") (pinfunction "1_1") (pintype "passive"))
      (node (ref "R63") (pin "1") (pinfunction "1_1") (pintype "passive"))
    )
    (net (code "16") (name "C1DOFF") (class "Default")
      (node (ref "D11") (pin "A") (pinfunction "ANODE_A") (pintype "passive"))
      (node (ref "R78") (pin "2") (pinfunction "2_2") (pintype "passive"))
      (node (ref "U17") (pin "B15") (pinfunction "B15_B15") (pintype "bidirectional"))
    )
    (net (code "17") (name "C1FET") (class "Default")
      (node (ref "R42") (pin "1") (pinfunction "1_1") (pintype "passive"))
      (node (ref "U21") (pin "2") (pinfunction "IN_2") (pintype "bidirectional"))
    )
    (net (code "18") (name "C1N") (class "Default")
      (node (ref "C44") (pin "2") (pinfunction "2_2") (pintype "passive"))
      (node (ref "L1") (pin "1") (pinfunction "P$1_1") (pintype "passive"))
      (node (ref "L5") (pin "P$1") (pinfunction "P$1_P$1") (pintype "passive"))
      (node (ref "Q10") (pin "5") (pinfunction "D_5") (pintype "bidirectional"))
      (node (ref "Q10") (pin "6") (pinfunction "D_6") (pintype "bidirectional"))
      (node (ref "Q10") (pin "7") (pinfunction "D_7") (pintype "bidirectional"))
      (node (ref "Q10") (pin "8") (pinfunction "D_8") (pintype "bidirectional"))
      (node (ref "Q2") (pin "1") (pinfunction "S_1") (pintype "bidirectional"))
      (node (ref "Q2") (pin "2") (pinfunction "S_2") (pintype "bidirectional"))
      (node (ref "Q2") (pin "3") (pinfunction "S_3") (pintype "bidirectional"))
      (node (ref "R5") (pin "1") (pinfunction "1_1") (pintype "passive"))
      (node (ref "U21") (pin "7") (pinfunction "SWN_7") (pintype "bidirectional"))
    )
    (net (code "19") (name "C1NGATE") (class "Default")
      (node (ref "C15") (pin "2") (pinfunction "2_2") (pintype "passive"))
      (node (ref "R35") (pin "2") (pinfunction "2_2") (pintype "passive"))
      (node (ref "R43") (pin "2") (pinfunction "2_2") (pintype "passive"))
      (node (ref "R50") (pin "1") (pinfunction "1_1") (pintype "passive"))
      (node (ref "U13") (pin "1") (pinfunction "VOUT_1") (pintype "bidirectional"))
    )
    (net (code "20") (name "C1ON") (class "Default")
      (node (ref "Q11") (pin "4") (pinfunction "G_4") (pintype "bidirectional"))
      (node (ref "R72") (pin "1") (pinfunction "1_1") (pintype "passive"))
      (node (ref "U17") (pin "B14") (pinfunction "B14_B14") (pintype "bidirectional"))
    )
    (net (code "21") (name "C1R") (class "Default")
      (node (ref "R37") (pin "1") (pinfunction "1_1") (pintype "passive"))
      (node (ref "R39") (pin "2") (pinfunction "2_2") (pintype "passive"))
      (node (ref "U17") (pin "A1") (pinfunction "A1_A1") (pintype "bidirectional"))
    )
    (net (code "22") (name "C1TH") (class "Default")
      (node (ref "C39") (pin "1") (pinfunction "1_1") (pintype "passive"))
      (node (ref "R7") (pin "1") (pinfunction "1_1") (pintype "passive"))
      (node (ref "R8") (pin "1") (pinfunction "1_1") (pintype "passive"))
      (node (ref "U17") (pin "A3") (pinfunction "A3_A3") (pintype "bidirectional"))
    )
    (net (code "23") (name "C1V") (class "Default")
      (node (ref "C51") (pin "1") (pinfunction "1_1") (pintype "passive"))
      (node (ref "R16") (pin "2") (pinfunction "2_2") (pintype "passive"))
      (node (ref "U17") (pin "B0") (pinfunction "B0_B0") (pintype "bidirectional"))
    )
    (net (code "24") (name "C2+") (class "Default")
      (node (ref "BAT3") (pin "1+") (pinfunction "C1+_1+") (pintype "bidirectional"))
      (node (ref "R57") (pin "2") (pinfunction "2_2") (pintype "passive"))
      (node (ref "R86") (pin "2") (pinfunction "2_2") (pintype "passive"))
      (node (ref "U8") (pin "4") (pinfunction "IN+_4") (pintype "bidirectional"))
    )
    (net (code "25") (name "C2-") (class "Default")
      (node (ref "BAT3") (pin "1-") (pinfunction "C1-_1-") (pintype "bidirectional"))
      (node (ref "F2") (pin "2") (pinfunction "2_2") (pintype "bidirectional"))
      (node (ref "F4") (pin "1") (pinfunction "1_1") (pintype "passive"))
      (node (ref "F6") (pin "K") (pinfunction "2_K") (pintype "bidirectional"))
      (node (ref "R38") (pin "2") (pinfunction "2_2") (pintype "passive"))
      (node (ref "R84") (pin "2") (pinfunction "2_2") (pintype "passive"))
    )
    (net (code "26") (name "C2A") (class "Default")
      (node (ref "C48") (pin "1") (pinfunction "1_1") (pintype "passive"))
      (node (ref "R24") (pin "2") (pinfunction "2_2") (pintype "passive"))
      (node (ref "TP8") (pin "1") (pinfunction "1_1") (pintype "bidirectional"))
      (node (ref "U17") (pin "A7") (pinfunction "A7_A7") (pintype "bidirectional"))
    )
    (net (code "27") (name "C2CCPWM") (class "Default")
      (node (ref "R69") (pin "1") (pinfunction "1_1") (pintype "passive"))
      (node (ref "R75") (pin "1") (pinfunction "1_1") (pintype "passive"))
      (node (ref "U17") (pin "B7") (pinfunction "B7_B7") (pintype "bidirectional"))
    )
    (net (code "28") (name "C2CCSET") (class "Default")
      (node (ref "C34") (pin "1") (pinfunction "1_1") (pintype "passive"))
      (node (ref "R59") (pin "1") (pinfunction "1_1") (pintype "passive"))
      (node (ref "R66") (pin "2") (pinfunction "2_2") (pintype "passive"))
      (node (ref "TP11") (pin "1") (pinfunction "1_1") (pintype "bidirectional"))
      (node (ref "U14") (pin "3") (pinfunction "VIN+_3") (pintype "bidirectional"))
    )
    (net (code "29") (name "C2COFF") (class "Default")
      (node (ref "R47") (pin "1") (pinfunction "1_1") (pintype "passive"))
      (node (ref "U3") (pin "3") (pinfunction "/OD_3") (pintype "bidirectional"))
    )
    (net (code "30") (name "C2DFB") (class "Default")
      (node (ref "Q8") (pin "3") (pinfunction "S_3") (pintype "bidirectional"))
      (node (ref "R3") (pin "1") (pinfunction "1_1") (pintype "passive"))
      (node (ref "R67") (pin "1") (pinfunction "1_1") (pintype "passive"))
    )
    (net (code "31") (name "C2DOFF") (class "Default")
      (node (ref "D12") (pin "A") (pinfunction "ANODE_A") (pintype "passive"))
      (node (ref "R79") (pin "2") (pinfunction "2_2") (pintype "passive"))
      (node (ref "U17") (pin "A15") (pinfunction "A15_A15") (pintype "bidirectional"))
    )
    (net (code "32") (name "C2FET") (class "Default")
      (node (ref "R46") (pin "1") (pinfunction "1_1") (pintype "passive"))
      (node (ref "U3") (pin "2") (pinfunction "IN_2") (pintype "bidirectional"))
    )
    (net (code "33") (name "C2N") (class "Default")
      (node (ref "C13") (pin "2") (pinfunction "2_2") (pintype "passive"))
      (node (ref "L2") (pin "1") (pinfunction "P$1_1") (pintype "passive"))
      (node (ref "L6") (pin "P$1") (pinfunction "P$1_P$1") (pintype "passive"))
      (node (ref "Q13") (pin "5") (pinfunction "D_5") (pintype "bidirectional"))
      (node (ref "Q13") (pin "6") (pinfunction "D_6") (pintype "bidirectional"))
      (node (ref "Q13") (pin "7") (pinfunction "D_7") (pintype "bidirectional"))
      (node (ref "Q13") (pin "8") (pinfunction "D_8") (pintype "bidirectional"))
      (node (ref "Q3") (pin "1") (pinfunction "S_1") (pintype "bidirectional"))
      (node (ref "Q3") (pin "2") (pinfunction "S_2") (pintype "bidirectional"))
      (node (ref "Q3") (pin "3") (pinfunction "S_3") (pintype "bidirectional"))
      (node (ref "R58") (pin "2") (pinfunction "2_2") (pintype "passive"))
      (node (ref "U3") (pin "7") (pinfunction "SWN_7") (pintype "bidirectional"))
    )
    (net (code "34") (name "C2NGATE") (class "Default")
      (node (ref "C33") (pin "2") (pinfunction "2_2") (pintype "passive"))
      (node (ref "R44") (pin "2") (pinfunction "2_2") (pintype "passive"))
      (node (ref "R51") (pin "1") (pinfunction "1_1") (pintype "passive"))
      (node (ref "R59") (pin "2") (pinfunction "2_2") (pintype "passive"))
      (node (ref "U14") (pin "1") (pinfunction "VOUT_1") (pintype "bidirectional"))
    )
    (net (code "35") (name "C2ON") (class "Default")
      (node (ref "Q12") (pin "4") (pinfunction "G_4") (pintype "bidirectional"))
      (node (ref "R73") (pin "1") (pinfunction "1_1") (pintype "passive"))
      (node (ref "U17") (pin "B3") (pinfunction "B3_B3") (pintype "bidirectional"))
    )
    (net (code "36") (name "C2R") (class "Default")
      (node (ref "R38") (pin "1") (pinfunction "1_1") (pintype "passive"))
      (node (ref "R40") (pin "2") (pinfunction "2_2") (pintype "passive"))
      (node (ref "U17") (pin "A0") (pinfunction "A0_A0") (pintype "bidirectional"))
    )
    (net (code "37") (name "C2TH") (class "Default")
      (node (ref "C40") (pin "1") (pinfunction "1_1") (pintype "passive"))
      (node (ref "R31") (pin "1") (pinfunction "1_1") (pintype "passive"))
      (node (ref "R32") (pin "1") (pinfunction "1_1") (pintype "passive"))
      (node (ref "U17") (pin "A2") (pinfunction "A2_A2") (pintype "bidirectional"))
    )
    (net (code "38") (name "C2V") (class "Default")
      (node (ref "C49") (pin "1") (pinfunction "1_1") (pintype "passive"))
      (node (ref "R33") (pin "2") (pinfunction "2_2") (pintype "passive"))
      (node (ref "U17") (pin "A6") (pinfunction "A6_A6") (pintype "bidirectional"))
    )
    (net (code "39") (name "DI") (class "Default")
      (node (ref "Q16") (pin "1") (pinfunction "G_1") (pintype "bidirectional"))
      (node (ref "U17") (pin "B13") (pinfunction "B13_B13") (pintype "bidirectional"))
    )
    (net (code "40") (name "DI2") (class "Default")
      (node (ref "LED7") (pin "2-DOUT") (pinfunction "DOUT_2-DOUT") (pintype "output"))
      (node (ref "LED8") (pin "4-DIN") (pinfunction "DIN_4-DIN") (pintype "input"))
    )
    (net (code "41") (name "FANON") (class "Default")
      (node (ref "Q9") (pin "1") (pinfunction "G_1") (pintype "bidirectional"))
      (node (ref "R34") (pin "2") (pinfunction "2_2") (pintype "passive"))
      (node (ref "U17") (pin "B4") (pinfunction "B4_B4") (pintype "bidirectional"))
    )
    (net (code "42") (name "GND") (class "Default")
      (node (ref "C10") (pin "-") (pinfunction "-_-") (pintype "passive"))
      (node (ref "C11") (pin "2") (pinfunction "2_2") (pintype "passive"))
      (node (ref "C12") (pin "2") (pinfunction "2_2") (pintype "passive"))
      (node (ref "C14") (pin "2") (pinfunction "2_2") (pintype "passive"))
      (node (ref "C16") (pin "2") (pinfunction "2_2") (pintype "passive"))
      (node (ref "C17") (pin "2") (pinfunction "2_2") (pintype "passive"))
      (node (ref "C18") (pin "2") (pinfunction "2_2") (pintype "passive"))
      (node (ref "C19") (pin "2") (pinfunction "2_2") (pintype "passive"))
      (node (ref "C20") (pin "2") (pinfunction "2_2") (pintype "passive"))
      (node (ref "C21") (pin "-") (pinfunction "-_-") (pintype "passive"))
      (node (ref "C22") (pin "-") (pinfunction "-_-") (pintype "passive"))
      (node (ref "C23") (pin "2") (pinfunction "2_2") (pintype "passive"))
      (node (ref "C24") (pin "2") (pinfunction "2_2") (pintype "passive"))
      (node (ref "C26") (pin "-") (pinfunction "-_-") (pintype "passive"))
      (node (ref "C27") (pin "2") (pinfunction "2_2") (pintype "passive"))
      (node (ref "C28") (pin "2") (pinfunction "2_2") (pintype "passive"))
      (node (ref "C29") (pin "2") (pinfunction "2_2") (pintype "passive"))
      (node (ref "C3") (pin "2") (pinfunction "2_2") (pintype "passive"))
      (node (ref "C30") (pin "2") (pinfunction "2_2") (pintype "passive"))
      (node (ref "C31") (pin "2") (pinfunction "2_2") (pintype "passive"))
      (node (ref "C32") (pin "2") (pinfunction "2_2") (pintype "passive"))
      (node (ref "C34") (pin "2") (pinfunction "2_2") (pintype "passive"))
      (node (ref "C35") (pin "2") (pinfunction "2_2") (pintype "passive"))
      (node (ref "C36") (pin "2") (pinfunction "2_2") (pintype "passive"))
      (node (ref "C37") (pin "2") (pinfunction "2_2") (pintype "passive"))
      (node (ref "C38") (pin "2") (pinfunction "2_2") (pintype "passive"))
      (node (ref "C39") (pin "2") (pinfunction "2_2") (pintype "passive"))
      (node (ref "C4") (pin "2") (pinfunction "2_2") (pintype "passive"))
      (node (ref "C40") (pin "2") (pinfunction "2_2") (pintype "passive"))
      (node (ref "C41") (pin "2") (pinfunction "2_2") (pintype "passive"))
      (node (ref "C42") (pin "2") (pinfunction "2_2") (pintype "passive"))
      (node (ref "C43") (pin "2") (pinfunction "2_2") (pintype "passive"))
      (node (ref "C45") (pin "2") (pinfunction "2_2") (pintype "passive"))
      (node (ref "C46") (pin "2") (pinfunction "2_2") (pintype "passive"))
      (node (ref "C48") (pin "2") (pinfunction "2_2") (pintype "passive"))
      (node (ref "C49") (pin "2") (pinfunction "2_2") (pintype "passive"))
      (node (ref "C5") (pin "2") (pinfunction "2_2") (pintype "passive"))
      (node (ref "C50") (pin "2") (pinfunction "2_2") (pintype "passive"))
      (node (ref "C51") (pin "2") (pinfunction "2_2") (pintype "passive"))
      (node (ref "C6") (pin "2") (pinfunction "2_2") (pintype "passive"))
      (node (ref "C7") (pin "-") (pinfunction "-_-") (pintype "passive"))
      (node (ref "C8") (pin "-") (pinfunction "-_-") (pintype "passive"))
      (node (ref "C9") (pin "2") (pinfunction "2_2") (pintype "passive"))
      (node (ref "D9") (pin "A") (pinfunction "ANODE_A") (pintype "passive"))
      (node (ref "J1") (pin "1") (pinfunction "1_1") (pintype "passive"))
      (node (ref "JP1") (pin "1") (pinfunction "1_1") (pintype "passive"))
      (node (ref "JP2") (pin "3") (pinfunction "3_3") (pintype "passive"))
      (node (ref "JP3") (pin "3") (pinfunction "3_3") (pintype "passive"))
      (node (ref "JP4") (pin "3") (pinfunction "3_3") (pintype "passive"))
      (node (ref "JP5") (pin "3") (pinfunction "3_3") (pintype "passive"))
      (node (ref "LCD1") (pin "1=GND") (pinfunction "GND_1=GND") (pintype "bidirectional"))
      (node (ref "LED7") (pin "3-GND") (pinfunction "GND_3-GND") (pintype "bidirectional"))
      (node (ref "LED8") (pin "3-GND") (pinfunction "GND_3-GND") (pintype "bidirectional"))
      (node (ref "Q10") (pin "1") (pinfunction "S_1") (pintype "bidirectional"))
      (node (ref "Q10") (pin "2") (pinfunction "S_2") (pintype "bidirectional"))
      (node (ref "Q10") (pin "3") (pinfunction "S_3") (pintype "bidirectional"))
      (node (ref "Q11") (pin "1") (pinfunction "S_1") (pintype "bidirectional"))
      (node (ref "Q11") (pin "2") (pinfunction "S_2") (pintype "bidirectional"))
      (node (ref "Q11") (pin "3") (pinfunction "S_3") (pintype "bidirectional"))
      (node (ref "Q12") (pin "1") (pinfunction "S_1") (pintype "bidirectional"))
      (node (ref "Q12") (pin "2") (pinfunction "S_2") (pintype "bidirectional"))
      (node (ref "Q12") (pin "3") (pinfunction "S_3") (pintype "bidirectional"))
      (node (ref "Q13") (pin "1") (pinfunction "S_1") (pintype "bidirectional"))
      (node (ref "Q13") (pin "2") (pinfunction "S_2") (pintype "bidirectional"))
      (node (ref "Q13") (pin "3") (pinfunction "S_3") (pintype "bidirectional"))
      (node (ref "Q16") (pin "2") (pinfunction "S_2") (pintype "bidirectional"))
      (node (ref "Q9") (pin "2") (pinfunction "S_2") (pintype "bidirectional"))
      (node (ref "R11") (pin "2") (pinfunction "2_2") (pintype "passive"))
      (node (ref "R13") (pin "1") (pinfunction "1_1") (pintype "passive"))
      (node (ref "R19") (pin "1") (pinfunction "1_1") (pintype "passive"))
      (node (ref "R2") (pin "2") (pinfunction "2_2") (pintype "passive"))
      (node (ref "R27") (pin "1") (pinfunction "1_1") (pintype "passive"))
      (node (ref "R3") (pin "2") (pinfunction "2_2") (pintype "passive"))
      (node (ref "R32") (pin "2") (pinfunction "2_2") (pintype "passive"))
      (node (ref "R34") (pin "1") (pinfunction "1_1") (pintype "passive"))
      (node (ref "R39") (pin "1") (pinfunction "1_1") (pintype "passive"))
      (node (ref "R4") (pin "2") (pinfunction "2_2") (pintype "passive"))
      (node (ref "R40") (pin "1") (pinfunction "1_1") (pintype "passive"))
      (node (ref "R49") (pin "2") (pinfunction "2_2") (pintype "passive"))
      (node (ref "R50") (pin "2") (pinfunction "2_2") (pintype "passive"))
      (node (ref "R51") (pin "2") (pinfunction "2_2") (pintype "passive"))
      (node (ref "R52") (pin "1") (pinfunction "1_1") (pintype "passive"))
      (node (ref "R56") (pin "2") (pinfunction "2_2") (pintype "passive"))
      (node (ref "R6") (pin "2") (pinfunction "2_2") (pintype "passive"))
      (node (ref "R60") (pin "2") (pinfunction "2_2") (pintype "passive"))
      (node (ref "R65") (pin "1") (pinfunction "1_1") (pintype "passive"))
      (node (ref "R70") (pin "1") (pinfunction "1_1") (pintype "passive"))
      (node (ref "R72") (pin "2") (pinfunction "2_2") (pintype "passive"))
      (node (ref "R73") (pin "2") (pinfunction "2_2") (pintype "passive"))
      (node (ref "R74") (pin "2") (pinfunction "2_2") (pintype "passive"))
      (node (ref "R75") (pin "2") (pinfunction "2_2") (pintype "passive"))
      (node (ref "R76") (pin "2") (pinfunction "2_2") (pintype "passive"))
      (node (ref "R8") (pin "2") (pinfunction "2_2") (pintype "passive"))
      (node (ref "R80") (pin "2") (pinfunction "2_2") (pintype "passive"))
      (node (ref "R81") (pin "2") (pinfunction "2_2") (pintype "passive"))
      (node (ref "R89") (pin "1") (pinfunction "1_1") (pintype "passive"))
      (node (ref "R94") (pin "1") (pinfunction "1_1") (pintype "passive"))
      (node (ref "S1") (pin "3") (pinfunction "3_3") (pintype "passive"))
      (node (ref "S1") (pin "4") (pinfunction "4_4") (pintype "passive"))
      (node (ref "S2") (pin "3") (pinfunction "3_3") (pintype "passive"))
      (node (ref "S2") (pin "4") (pinfunction "4_4") (pintype "passive"))
      (node (ref "T1") (pin "1") (pinfunction "1_1") (pintype "bidirectional"))
      (node (ref "T2") (pin "1") (pinfunction "1_1") (pintype "bidirectional"))
      (node (ref "U1") (pin "2") (pinfunction "GND_2") (pintype "bidirectional"))
      (node (ref "U12") (pin "4") (pinfunction "GND_4") (pintype "bidirectional"))
      (node (ref "U13") (pin "2") (pinfunction "VSS_2") (pintype "bidirectional"))
      (node (ref "U14") (pin "2") (pinfunction "VSS_2") (pintype "bidirectional"))
      (node (ref "U15") (pin "2") (pinfunction "GND_2") (pintype "bidirectional"))
      (node (ref "U16") (pin "2") (pinfunction "GND_2") (pintype "bidirectional"))
      (node (ref "U16") (pin "2@1") (pinfunction "GND_2@1") (pintype "bidirectional"))
      (node (ref "U17") (pin "GND") (pinfunction "GND_GND") (pintype "bidirectional"))
      (node (ref "U17") (pin "GND2") (pinfunction "GND2_GND2") (pintype "bidirectional"))
      (node (ref "U17") (pin "GND4") (pinfunction "GND4_GND4") (pintype "bidirectional"))
      (node (ref "U18") (pin "2") (pinfunction "GND_2") (pintype "bidirectional"))
      (node (ref "U21") (pin "6") (pinfunction "PGND_6") (pintype "bidirectional"))
      (node (ref "U3") (pin "6") (pinfunction "PGND_6") (pintype "bidirectional"))
      (node (ref "U4") (pin "2") (pinfunction "VSS_2") (pintype "bidirectional"))
      (node (ref "U5") (pin "2") (pinfunction "GND_2") (pintype "bidirectional"))
      (node (ref "U6") (pin "3") (pinfunction "A_3") (pintype "passive"))
      (node (ref "U8") (pin "2") (pinfunction "GND_2") (pintype "bidirectional"))
      (node (ref "U9") (pin "2") (pinfunction "VSS_2") (pintype "bidirectional"))
    )
    (net (code "43") (name "HSTH") (class "Default")
      (node (ref "C41") (pin "1") (pinfunction "1_1") (pintype "passive"))
      (node (ref "R77") (pin "1") (pinfunction "1_1") (pintype "passive"))
      (node (ref "T1") (pin "2") (pinfunction "2_2") (pintype "bidirectional"))
      (node (ref "U18") (pin "1") (pinfunction "2_1") (pintype "bidirectional"))
    )
    (net (code "44") (name "HSTH2") (class "Default")
      (node (ref "C43") (pin "1") (pinfunction "1_1") (pintype "passive"))
      (node (ref "R14") (pin "1") (pinfunction "1_1") (pintype "passive"))
      (node (ref "T2") (pin "2") (pinfunction "2_2") (pintype "bidirectional"))
      (node (ref "U15") (pin "3") (pinfunction "1_3") (pintype "bidirectional"))
    )
    (net (code "45") (name "ISNS_REF") (class "Default")
      (node (ref "C11") (pin "1") (pinfunction "1_1") (pintype "passive"))
      (node (ref "C16") (pin "1") (pinfunction "1_1") (pintype "passive"))
      (node (ref "C28") (pin "1") (pinfunction "1_1") (pintype "passive"))
      (node (ref "R10") (pin "2") (pinfunction "2_2") (pintype "passive"))
      (node (ref "R11") (pin "1") (pinfunction "1_1") (pintype "passive"))
      (node (ref "TP5") (pin "1") (pinfunction "1_1") (pintype "bidirectional"))
      (node (ref "TP7") (pin "1") (pinfunction "1_1") (pintype "bidirectional"))
      (node (ref "U1") (pin "1") (pinfunction "REF_1") (pintype "bidirectional"))
      (node (ref "U17") (pin "A5") (pinfunction "A5_A5") (pintype "bidirectional"))
      (node (ref "U8") (pin "1") (pinfunction "REF_1") (pintype "bidirectional"))
    )
    (net (code "46") (name "NGATE1") (class "Default")
      (node (ref "LED4") (pin "A") (pinfunction "A_A") (pintype "passive"))
      (node (ref "Q10") (pin "4") (pinfunction "G_4") (pintype "bidirectional"))
      (node (ref "R56") (pin "1") (pinfunction "1_1") (pintype "passive"))
      (node (ref "U21") (pin "5") (pinfunction "DRVL_5") (pintype "bidirectional"))
    )
    (net (code "47") (name "NGATE2") (class "Default")
      (node (ref "LED5") (pin "A") (pinfunction "A_A") (pintype "passive"))
      (node (ref "Q13") (pin "4") (pinfunction "G_4") (pintype "bidirectional"))
      (node (ref "R60") (pin "1") (pinfunction "1_1") (pintype "passive"))
      (node (ref "U3") (pin "5") (pinfunction "DRVL_5") (pintype "bidirectional"))
    )
    (net (code "48") (name "Net-(C15-Pad1)") (class "Default")
      (node (ref "C15") (pin "1") (pinfunction "1_1") (pintype "passive"))
      (node (ref "R64") (pin "2") (pinfunction "2_2") (pintype "passive"))
    )
    (net (code "49") (name "Net-(C33-Pad1)") (class "Default")
      (node (ref "C33") (pin "1") (pinfunction "1_1") (pintype "passive"))
      (node (ref "R68") (pin "2") (pinfunction "2_2") (pintype "passive"))
    )
    (net (code "50") (name "Net-(D1-CATHODE)") (class "Default")
      (node (ref "C13") (pin "1") (pinfunction "1_1") (pintype "passive"))
      (node (ref "D1") (pin "K") (pinfunction "CATHODE_K") (pintype "passive"))
      (node (ref "U3") (pin "1") (pinfunction "BST_1") (pintype "bidirectional"))
    )
    (net (code "51") (name "Net-(D11-CATHODE)") (class "Default")
      (node (ref "D11") (pin "K") (pinfunction "CATHODE_K") (pintype "passive"))
      (node (ref "R63") (pin "2") (pinfunction "2_2") (pintype "passive"))
      (node (ref "R64") (pin "1") (pinfunction "1_1") (pintype "passive"))
      (node (ref "U13") (pin "4") (pinfunction "VIN-_4") (pintype "bidirectional"))
    )
    (net (code "52") (name "Net-(D12-CATHODE)") (class "Default")
      (node (ref "D12") (pin "K") (pinfunction "CATHODE_K") (pintype "passive"))
      (node (ref "R67") (pin "2") (pinfunction "2_2") (pintype "passive"))
      (node (ref "R68") (pin "1") (pinfunction "1_1") (pintype "passive"))
      (node (ref "U14") (pin "4") (pinfunction "VIN-_4") (pintype "bidirectional"))
    )
    (net (code "53") (name "Net-(D20-CATHODE)") (class "Default")
      (node (ref "C44") (pin "1") (pinfunction "1_1") (pintype "passive"))
      (node (ref "D20") (pin "K") (pinfunction "CATHODE_K") (pintype "passive"))
      (node (ref "U21") (pin "1") (pinfunction "BST_1") (pintype "bidirectional"))
    )
    (net (code "54") (name "Net-(F5-1)") (class "Default")
      (node (ref "F1") (pin "1") (pinfunction "1_1") (pintype "bidirectional"))
      (node (ref "F3") (pin "2") (pinfunction "2_2") (pintype "passive"))
      (node (ref "F5") (pin "A") (pinfunction "1_A") (pintype "bidirectional"))
      (node (ref "Q11") (pin "5") (pinfunction "D_5") (pintype "bidirectional"))
      (node (ref "Q11") (pin "6") (pinfunction "D_6") (pintype "bidirectional"))
      (node (ref "Q11") (pin "7") (pinfunction "D_7") (pintype "bidirectional"))
      (node (ref "Q11") (pin "8") (pinfunction "D_8") (pintype "bidirectional"))
    )
    (net (code "55") (name "Net-(F6-1)") (class "Default")
      (node (ref "F2") (pin "1") (pinfunction "1_1") (pintype "bidirectional"))
      (node (ref "F4") (pin "2") (pinfunction "2_2") (pintype "passive"))
      (node (ref "F6") (pin "A") (pinfunction "1_A") (pintype "bidirectional"))
      (node (ref "Q12") (pin "5") (pinfunction "D_5") (pintype "bidirectional"))
      (node (ref "Q12") (pin "6") (pinfunction "D_6") (pintype "bidirectional"))
      (node (ref "Q12") (pin "7") (pinfunction "D_7") (pintype "bidirectional"))
      (node (ref "Q12") (pin "8") (pinfunction "D_8") (pintype "bidirectional"))
    )
    (net (code "56") (name "Net-(J1-Pad2)") (class "Default")
      (node (ref "J1") (pin "2") (pinfunction "2_2") (pintype "passive"))
      (node (ref "R22") (pin "1") (pinfunction "1_1") (pintype "passive"))
    )
    (net (code "57") (name "Net-(L1-P$2)") (class "Default")
      (node (ref "C26") (pin "+") (pinfunction "+_+") (pintype "passive"))
      (node (ref "C5") (pin "1") (pinfunction "1_1") (pintype "passive"))
      (node (ref "C8") (pin "+") (pinfunction "+_+") (pintype "passive"))
      (node (ref "L1") (pin "2") (pinfunction "P$2_2") (pintype "passive"))
      (node (ref "L5") (pin "P$2") (pinfunction "P$2_P$2") (pintype "passive"))
      (node (ref "Q7") (pin "2") (pinfunction "D_2") (pintype "bidirectional"))
      (node (ref "R1") (pin "2") (pinfunction "2_2") (pintype "passive"))
    )
    (net (code "58") (name "Net-(L2-P$2)") (class "Default")
      (node (ref "C20") (pin "1") (pinfunction "1_1") (pintype "passive"))
      (node (ref "C21") (pin "+") (pinfunction "+_+") (pintype "passive"))
      (node (ref "C22") (pin "+") (pinfunction "+_+") (pintype "passive"))
      (node (ref "L2") (pin "2") (pinfunction "P$2_2") (pintype "passive"))
      (node (ref "L6") (pin "P$2") (pinfunction "P$2_P$2") (pintype "passive"))
      (node (ref "Q8") (pin "2") (pinfunction "D_2") (pintype "bidirectional"))
      (node (ref "R17") (pin "2") (pinfunction "2_2") (pintype "passive"))
    )
    (net (code "59") (name "Net-(L3-P$1)") (class "Default")
      (node (ref "C25") (pin "2") (pinfunction "2_2") (pintype "passive"))
      (node (ref "L3") (pin "1") (pinfunction "P$1_1") (pintype "passive"))
      (node (ref "U5") (pin "6") (pinfunction "SW_6") (pintype "bidirectional"))
    )
    (net (code "60") (name "Net-(LED3-PadC)") (class "Default")
      (node (ref "LED3") (pin "C") (pinfunction "C_C") (pintype "passive"))
      (node (ref "R88") (pin "2") (pinfunction "2_2") (pintype "passive"))
    )
    (net (code "61") (name "Net-(LED4-PadC)") (class "Default")
      (node (ref "LED4") (pin "C") (pinfunction "C_C") (pintype "passive"))
      (node (ref "R52") (pin "2") (pinfunction "2_2") (pintype "passive"))
    )
    (net (code "62") (name "Net-(LED5-PadC)") (class "Default")
      (node (ref "LED5") (pin "C") (pinfunction "C_C") (pintype "passive"))
      (node (ref "R89") (pin "2") (pinfunction "2_2") (pintype "passive"))
    )
    (net (code "63") (name "Net-(LED6-PadC)") (class "Default")
      (node (ref "LED6") (pin "C") (pinfunction "C_C") (pintype "passive"))
      (node (ref "R90") (pin "2") (pinfunction "2_2") (pintype "passive"))
    )
    (net (code "64") (name "Net-(LED7-DIN)") (class "Default")
      (node (ref "LED7") (pin "4-DIN") (pinfunction "DIN_4-DIN") (pintype "input"))
      (node (ref "Q16") (pin "3") (pinfunction "D_3") (pintype "bidirectional"))
      (node (ref "R41") (pin "2") (pinfunction "2_2") (pintype "passive"))
    )
    (net (code "65") (name "Net-(LED8-DOUT)") (class "Default")
      (node (ref "JP8") (pin "1") (pinfunction "1_1") (pintype "passive"))
      (node (ref "LED8") (pin "2-DOUT") (pinfunction "DOUT_2-DOUT") (pintype "output"))
    )
    (net (code "66") (name "Net-(Q7-G)") (class "Default")
      (node (ref "Q7") (pin "1") (pinfunction "G_1") (pintype "bidirectional"))
      (node (ref "R43") (pin "1") (pinfunction "1_1") (pintype "passive"))
    )
    (net (code "67") (name "Net-(Q8-G)") (class "Default")
      (node (ref "Q8") (pin "1") (pinfunction "G_1") (pintype "bidirectional"))
      (node (ref "R44") (pin "1") (pinfunction "1_1") (pintype "passive"))
    )
    (net (code "68") (name "Net-(Q9-D)") (class "Default")
      (node (ref "J2") (pin "2") (pinfunction "2_2") (pintype "passive"))
      (node (ref "Q9") (pin "3") (pinfunction "D_3") (pintype "bidirectional"))
    )
    (net (code "69") (name "Net-(R61-Pad1)") (class "Default")
      (node (ref "R61") (pin "1") (pinfunction "1_1") (pintype "passive"))
      (node (ref "R62") (pin "2") (pinfunction "2_2") (pintype "passive"))
      (node (ref "R65") (pin "2") (pinfunction "2_2") (pintype "passive"))
    )
    (net (code "70") (name "Net-(R66-Pad1)") (class "Default")
      (node (ref "R66") (pin "1") (pinfunction "1_1") (pintype "passive"))
      (node (ref "R69") (pin "2") (pinfunction "2_2") (pintype "passive"))
      (node (ref "R70") (pin "2") (pinfunction "2_2") (pintype "passive"))
    )
    (net (code "71") (name "Net-(TP1-1)") (class "Default")
      (node (ref "R55") (pin "2") (pinfunction "2_2") (pintype "passive"))
      (node (ref "TP1") (pin "P$1") (pinfunction "1_P$1") (pintype "bidirectional"))
    )
    (net (code "72") (name "Net-(TP2-1)") (class "Default")
      (node (ref "R83") (pin "2") (pinfunction "2_2") (pintype "passive"))
      (node (ref "TP2") (pin "P$1") (pinfunction "1_P$1") (pintype "bidirectional"))
    )
    (net (code "73") (name "Net-(TP3-1)") (class "Default")
      (node (ref "R85") (pin "2") (pinfunction "2_2") (pintype "passive"))
      (node (ref "TP3") (pin "P$1") (pinfunction "1_P$1") (pintype "bidirectional"))
    )
    (net (code "74") (name "Net-(TP4-1)") (class "Default")
      (node (ref "R87") (pin "2") (pinfunction "2_2") (pintype "passive"))
      (node (ref "TP4") (pin "P$1") (pinfunction "1_P$1") (pintype "bidirectional"))
    )
    (net (code "75") (name "Net-(U1-IN-)") (class "Default")
      (node (ref "R1") (pin "1") (pinfunction "1_1") (pintype "passive"))
      (node (ref "R30") (pin "1") (pinfunction "1_1") (pintype "passive"))
      (node (ref "U1") (pin "5") (pinfunction "IN-_5") (pintype "bidirectional"))
    )
    (net (code "76") (name "Net-(U1-OUT)") (class "Default")
      (node (ref "R12") (pin "1") (pinfunction "1_1") (pintype "passive"))
      (node (ref "U1") (pin "6") (pinfunction "OUT_6") (pintype "bidirectional"))
    )
    (net (code "77") (name "Net-(U4-VIN+)") (class "Default")
      (node (ref "R18") (pin "2") (pinfunction "2_2") (pintype "passive"))
      (node (ref "R19") (pin "2") (pinfunction "2_2") (pintype "passive"))
      (node (ref "U4") (pin "1") (pinfunction "VIN+_1") (pintype "bidirectional"))
    )
    (net (code "78") (name "Net-(U4-VIN-)") (class "Default")
      (node (ref "R20") (pin "2") (pinfunction "2_2") (pintype "passive"))
      (node (ref "R21") (pin "1") (pinfunction "1_1") (pintype "passive"))
      (node (ref "U4") (pin "3") (pinfunction "VIN-_3") (pintype "bidirectional"))
    )
    (net (code "79") (name "Net-(U4-VOUT)") (class "Default")
      (node (ref "R16") (pin "1") (pinfunction "1_1") (pintype "passive"))
      (node (ref "R21") (pin "2") (pinfunction "2_2") (pintype "passive"))
      (node (ref "U4") (pin "4") (pinfunction "VOUT_4") (pintype "bidirectional"))
    )
    (net (code "80") (name "Net-(U5-BST)") (class "Default")
      (node (ref "C25") (pin "1") (pinfunction "1_1") (pintype "passive"))
      (node (ref "U5") (pin "1") (pinfunction "BST_1") (pintype "bidirectional"))
    )
    (net (code "81") (name "Net-(U5-EN)") (class "Default")
      (node (ref "R95") (pin "1") (pinfunction "1_1") (pintype "passive"))
      (node (ref "U5") (pin "4") (pinfunction "EN_4") (pintype "bidirectional"))
    )
    (net (code "82") (name "Net-(U5-FB)") (class "Default")
      (node (ref "R93") (pin "1") (pinfunction "1_1") (pintype "passive"))
      (node (ref "R94") (pin "2") (pinfunction "2_2") (pintype "passive"))
      (node (ref "U5") (pin "3") (pinfunction "FB_3") (pintype "bidirectional"))
    )
    (net (code "83") (name "Net-(U8-IN-)") (class "Default")
      (node (ref "R17") (pin "1") (pinfunction "1_1") (pintype "passive"))
      (node (ref "R57") (pin "1") (pinfunction "1_1") (pintype "passive"))
      (node (ref "U8") (pin "5") (pinfunction "IN-_5") (pintype "bidirectional"))
    )
    (net (code "84") (name "Net-(U8-OUT)") (class "Default")
      (node (ref "R24") (pin "1") (pinfunction "1_1") (pintype "passive"))
      (node (ref "U8") (pin "6") (pinfunction "OUT_6") (pintype "bidirectional"))
    )
    (net (code "85") (name "Net-(U9-VIN+)") (class "Default")
      (node (ref "R26") (pin "2") (pinfunction "2_2") (pintype "passive"))
      (node (ref "R27") (pin "2") (pinfunction "2_2") (pintype "passive"))
      (node (ref "U9") (pin "1") (pinfunction "VIN+_1") (pintype "bidirectional"))
    )
    (net (code "86") (name "Net-(U9-VIN-)") (class "Default")
      (node (ref "R28") (pin "2") (pinfunction "2_2") (pintype "passive"))
      (node (ref "R29") (pin "1") (pinfunction "1_1") (pintype "passive"))
      (node (ref "U9") (pin "3") (pinfunction "VIN-_3") (pintype "bidirectional"))
    )
    (net (code "87") (name "Net-(U9-VOUT)") (class "Default")
      (node (ref "R29") (pin "2") (pinfunction "2_2") (pintype "passive"))
      (node (ref "R33") (pin "1") (pinfunction "1_1") (pintype "passive"))
      (node (ref "U9") (pin "4") (pinfunction "VOUT_4") (pintype "bidirectional"))
    )
    (net (code "88") (name "Net-(U12-A0)") (class "Default")
      (node (ref "JP3") (pin "2") (pinfunction "2_2") (pintype "passive"))
      (node (ref "U12") (pin "7") (pinfunction "A0_7") (pintype "bidirectional"))
    )
    (net (code "89") (name "Net-(U12-A1)") (class "Default")
      (node (ref "JP4") (pin "2") (pinfunction "2_2") (pintype "passive"))
      (node (ref "U12") (pin "6") (pinfunction "A1_6") (pintype "bidirectional"))
    )
    (net (code "90") (name "Net-(U12-A2)") (class "Default")
      (node (ref "JP5") (pin "2") (pinfunction "2_2") (pintype "passive"))
      (node (ref "U12") (pin "5") (pinfunction "A2_5") (pintype "bidirectional"))
    )
    (net (code "91") (name "Net-(U17-A12{slash}D+)") (class "Default")
      (node (ref "R53") (pin "2") (pinfunction "2_2") (pintype "passive"))
      (node (ref "U17") (pin "A12") (pinfunction "A12/D+_A12") (pintype "bidirectional"))
    )
    (net (code "92") (name "OA1+") (class "Default")
      (node (ref "R18") (pin "1") (pinfunction "1_1") (pintype "passive"))
      (node (ref "R82") (pin "1") (pinfunction "1_1") (pintype "passive"))
      (node (ref "R83") (pin "1") (pinfunction "1_1") (pintype "passive"))
    )
    (net (code "93") (name "OA1-") (class "Default")
      (node (ref "R20") (pin "1") (pinfunction "1_1") (pintype "passive"))
      (node (ref "R54") (pin "1") (pinfunction "1_1") (pintype "passive"))
      (node (ref "R55") (pin "1") (pinfunction "1_1") (pintype "passive"))
    )
    (net (code "94") (name "OA2+") (class "Default")
      (node (ref "R26") (pin "1") (pinfunction "1_1") (pintype "passive"))
      (node (ref "R86") (pin "1") (pinfunction "1_1") (pintype "passive"))
      (node (ref "R87") (pin "1") (pinfunction "1_1") (pintype "passive"))
    )
    (net (code "95") (name "OA2-") (class "Default")
      (node (ref "R28") (pin "1") (pinfunction "1_1") (pintype "passive"))
      (node (ref "R84") (pin "1") (pinfunction "1_1") (pintype "passive"))
      (node (ref "R85") (pin "1") (pinfunction "1_1") (pintype "passive"))
    )
    (net (code "96") (name "PA8") (class "Default")
      (node (ref "R42") (pin "2") (pinfunction "2_2") (pintype "passive"))
      (node (ref "R80") (pin "1") (pinfunction "1_1") (pintype "passive"))
      (node (ref "U17") (pin "A8") (pinfunction "A8_A8") (pintype "bidirectional"))
    )
    (net (code "97") (name "PA9") (class "Default")
      (node (ref "R4") (pin "1") (pinfunction "1_1") (pintype "passive"))
      (node (ref "R45") (pin "2") (pinfunction "2_2") (pintype "passive"))
      (node (ref "U17") (pin "A9") (pinfunction "A9_A9") (pintype "bidirectional"))
    )
    (net (code "98") (name "PA10") (class "Default")
      (node (ref "R46") (pin "2") (pinfunction "2_2") (pintype "passive"))
      (node (ref "R81") (pin "1") (pinfunction "1_1") (pintype "passive"))
      (node (ref "U17") (pin "A10") (pinfunction "A10_A10") (pintype "bidirectional"))
    )
    (net (code "99") (name "PB5") (class "Default")
      (node (ref "JP6") (pin "3") (pinfunction "3_3") (pintype "passive"))
      (node (ref "JP7") (pin "1") (pinfunction "1_1") (pintype "passive"))
      (node (ref "R49") (pin "1") (pinfunction "1_1") (pintype "passive"))
      (node (ref "U15") (pin "6") (pinfunction "SEL_6") (pintype "bidirectional"))
      (node (ref "U17") (pin "B5") (pinfunction "B5_B5") (pintype "bidirectional"))
    )
    (net (code "100") (name "PB8") (class "Default")
      (node (ref "R47") (pin "2") (pinfunction "2_2") (pintype "passive"))
      (node (ref "R6") (pin "1") (pinfunction "1_1") (pintype "passive"))
      (node (ref "U17") (pin "B8") (pinfunction "B8_B8") (pintype "bidirectional"))
    )
    (net (code "101") (name "PB12") (class "Default")
      (node (ref "R76") (pin "1") (pinfunction "1_1") (pintype "passive"))
      (node (ref "U17") (pin "B12") (pinfunction "B12_B12") (pintype "bidirectional"))
      (node (ref "U18") (pin "6") (pinfunction "SEL_6") (pintype "bidirectional"))
    )
    (net (code "102") (name "PGATE1") (class "Default")
      (node (ref "Q2") (pin "4") (pinfunction "G_4") (pintype "bidirectional"))
      (node (ref "R5") (pin "2") (pinfunction "2_2") (pintype "passive"))
      (node (ref "R88") (pin "1") (pinfunction "1_1") (pintype "passive"))
      (node (ref "U21") (pin "8") (pinfunction "DRVH_8") (pintype "bidirectional"))
    )
    (net (code "103") (name "PGATE2") (class "Default")
      (node (ref "Q3") (pin "4") (pinfunction "G_4") (pintype "bidirectional"))
      (node (ref "R58") (pin "1") (pinfunction "1_1") (pintype "passive"))
      (node (ref "R90") (pin "1") (pinfunction "1_1") (pintype "passive"))
      (node (ref "U3") (pin "8") (pinfunction "DRVH_8") (pintype "bidirectional"))
    )
    (net (code "104") (name "S1") (class "Default")
      (node (ref "S1") (pin "1") (pinfunction "1_1") (pintype "passive"))
      (node (ref "S1") (pin "2") (pinfunction "2_2") (pintype "passive"))
      (node (ref "U17") (pin "B9") (pinfunction "B9_B9") (pintype "bidirectional"))
    )
    (net (code "105") (name "S2") (class "Default")
      (node (ref "S2") (pin "1") (pinfunction "1_1") (pintype "passive"))
      (node (ref "S2") (pin "2") (pinfunction "2_2") (pintype "passive"))
      (node (ref "U17") (pin "C13") (pinfunction "C13_C13") (pintype "bidirectional"))
    )
    (net (code "106") (name "SCL-TX") (class "Default")
      (node (ref "JP1") (pin "2") (pinfunction "2_2") (pintype "passive"))
      (node (ref "JP2") (pin "2") (pinfunction "2_2") (pintype "passive"))
      (node (ref "LCD1") (pin "3=SCL") (pinfunction "SCL_3=SCL") (pintype "bidirectional"))
      (node (ref "U12") (pin "2") (pinfunction "SCL_2") (pintype "bidirectional"))
      (node (ref "U17") (pin "B10") (pinfunction "B10_B10") (pintype "bidirectional"))
    )
    (net (code "107") (name "SDA-RX") (class "Default")
      (node (ref "JP1") (pin "3") (pinfunction "3_3") (pintype "passive"))
      (node (ref "JP2") (pin "1") (pinfunction "1_1") (pintype "passive"))
      (node (ref "LCD1") (pin "4-SDA") (pinfunction "SDA_4-SDA") (pintype "bidirectional"))
      (node (ref "U12") (pin "1") (pinfunction "SDA_1") (pintype "bidirectional"))
      (node (ref "U17") (pin "B11") (pinfunction "B11_B11") (pintype "bidirectional"))
    )
    (net (code "108") (name "unconnected-(U12-OS-Pad3)") (class "Default")
      (node (ref "U12") (pin "3") (pinfunction "OS_3") (pintype "bidirectional"))
    )
    (net (code "109") (name "unconnected-(U17-PadRST)") (class "Default")
      (node (ref "U17") (pin "RST") (pinfunction "RST_RST") (pintype "bidirectional"))
    )
    (net (code "110") (name "unconnected-(U17-VB-PadVBAT)") (class "Default")
      (node (ref "U17") (pin "VBAT") (pinfunction "VB_VBAT") (pintype "bidirectional"))
    )
  )
)
